# draft5_4lyr.net
KiCad netlist of a schematic drawn in EAGLE
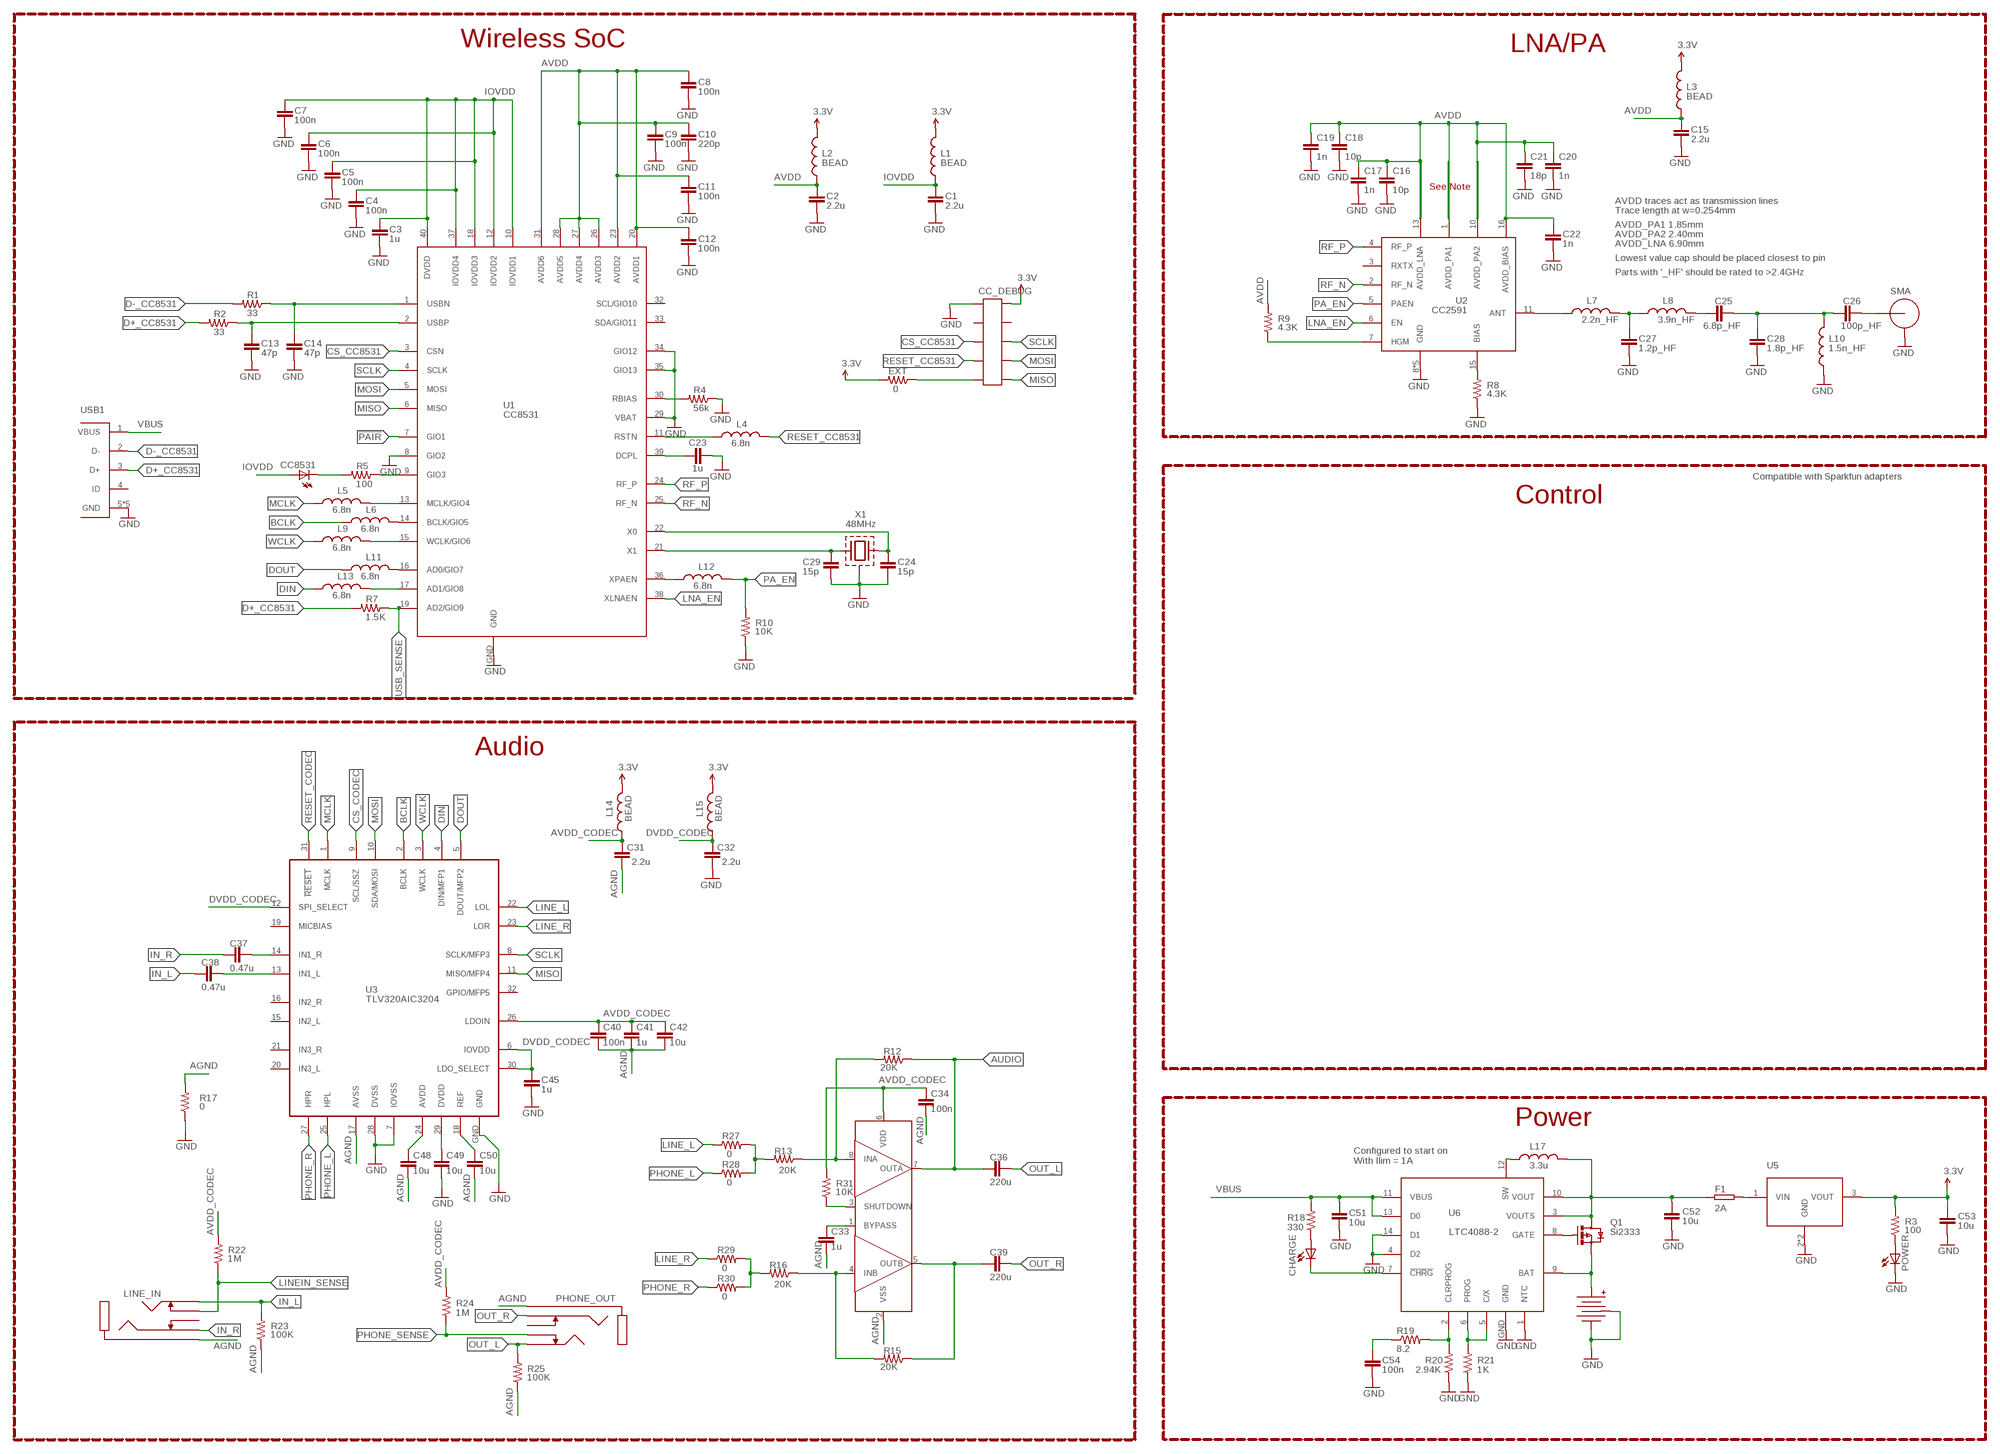
[diagram p0: schematic, sheet 1, part 1 of 2]
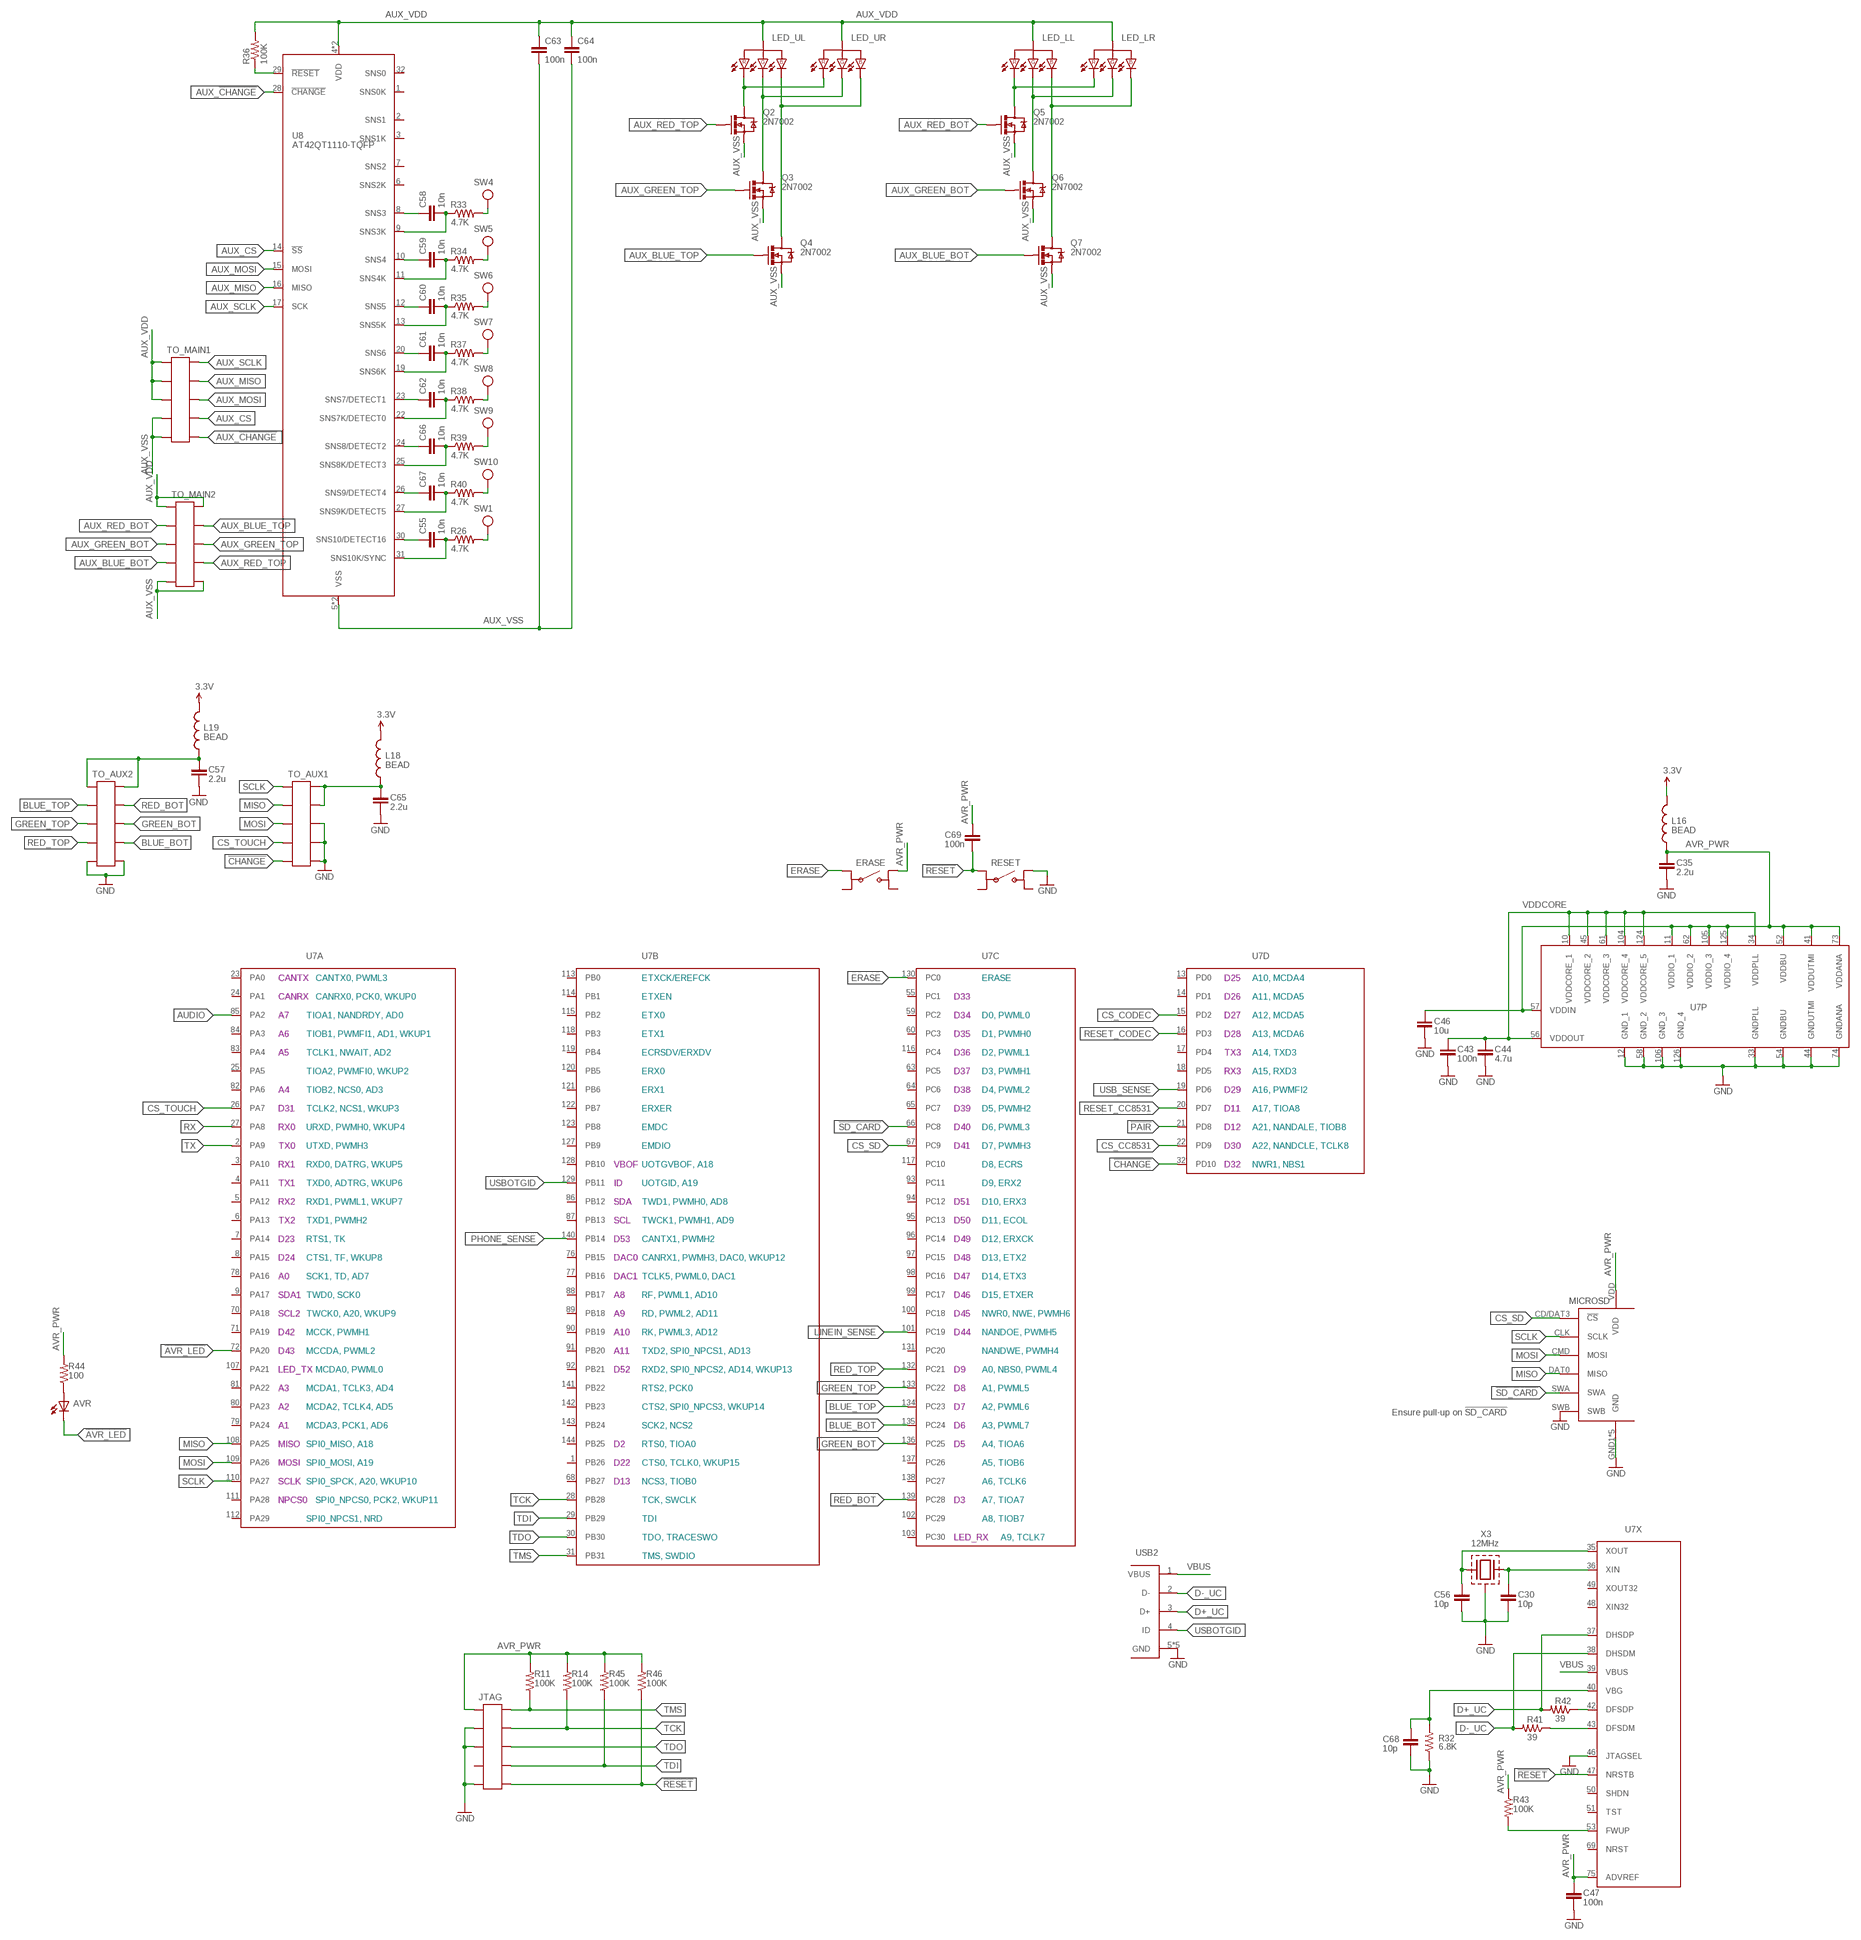
[diagram p1: schematic, sheet 1, part 2 of 2]

(export (version "E")
  (design (tool "Eeschema 10.0.6"))
  (components
    (comp (ref "AVR")
      (value "LED1206")
      (footprint "eagle-import:LED-1206")
      (libsource (lib "eagle-import") (part "LED1206"))
    )
    (comp (ref "BATTERY")
      (value "BATTERY-LIPO-JST")
      (footprint "eagle-import:1775469-2")
      (libsource (lib "eagle-import") (part "BATTERY-LIPO-JST"))
    )
    (comp (ref "C1")
      (value "2.2u")
      (footprint "eagle-import:C0603")
      (libsource (lib "eagle-import") (part "rcl_C-EUC0603"))
    )
    (comp (ref "C2")
      (value "2.2u")
      (footprint "eagle-import:C0603")
      (libsource (lib "eagle-import") (part "rcl_C-EUC0603"))
    )
    (comp (ref "C3")
      (value "1u")
      (footprint "eagle-import:C0603")
      (libsource (lib "eagle-import") (part "rcl_C-EUC0603"))
    )
    (comp (ref "C4")
      (value "100n")
      (footprint "eagle-import:C0603")
      (libsource (lib "eagle-import") (part "rcl_C-EUC0603"))
    )
    (comp (ref "C5")
      (value "100n")
      (footprint "eagle-import:C0603")
      (libsource (lib "eagle-import") (part "rcl_C-EUC0603"))
    )
    (comp (ref "C6")
      (value "100n")
      (footprint "eagle-import:C0603")
      (libsource (lib "eagle-import") (part "rcl_C-EUC0603"))
    )
    (comp (ref "C7")
      (value "100n")
      (footprint "eagle-import:C0603")
      (libsource (lib "eagle-import") (part "rcl_C-EUC0603"))
    )
    (comp (ref "C8")
      (value "100n")
      (footprint "eagle-import:C0603")
      (libsource (lib "eagle-import") (part "rcl_C-EUC0603"))
    )
    (comp (ref "C9")
      (value "100n")
      (footprint "eagle-import:C0603")
      (libsource (lib "eagle-import") (part "rcl_C-EUC0603"))
    )
    (comp (ref "C10")
      (value "220p")
      (footprint "eagle-import:C0603")
      (libsource (lib "eagle-import") (part "rcl_C-EUC0603"))
    )
    (comp (ref "C11")
      (value "100n")
      (footprint "eagle-import:C0603")
      (libsource (lib "eagle-import") (part "rcl_C-EUC0603"))
    )
    (comp (ref "C12")
      (value "100n")
      (footprint "eagle-import:C0603")
      (libsource (lib "eagle-import") (part "rcl_C-EUC0603"))
    )
    (comp (ref "C13")
      (value "47p")
      (footprint "eagle-import:C0603")
      (libsource (lib "eagle-import") (part "rcl_C-EUC0603"))
    )
    (comp (ref "C14")
      (value "47p")
      (footprint "eagle-import:C0603")
      (libsource (lib "eagle-import") (part "rcl_C-EUC0603"))
    )
    (comp (ref "C15")
      (value "2.2u")
      (footprint "eagle-import:C0603")
      (libsource (lib "eagle-import") (part "rcl_C-EUC0603"))
    )
    (comp (ref "C16")
      (value "10p")
      (footprint "eagle-import:C0603")
      (libsource (lib "eagle-import") (part "rcl_C-EUC0603"))
    )
    (comp (ref "C17")
      (value "1n")
      (footprint "eagle-import:C0603")
      (libsource (lib "eagle-import") (part "rcl_C-EUC0603"))
    )
    (comp (ref "C18")
      (value "10p")
      (footprint "eagle-import:C0603")
      (libsource (lib "eagle-import") (part "rcl_C-EUC0603"))
    )
    (comp (ref "C19")
      (value "1n")
      (footprint "eagle-import:C0603")
      (libsource (lib "eagle-import") (part "rcl_C-EUC0603"))
    )
    (comp (ref "C20")
      (value "1n")
      (footprint "eagle-import:C0603")
      (libsource (lib "eagle-import") (part "rcl_C-EUC0603"))
    )
    (comp (ref "C21")
      (value "18p")
      (footprint "eagle-import:C0603")
      (libsource (lib "eagle-import") (part "rcl_C-EUC0603"))
    )
    (comp (ref "C22")
      (value "1n")
      (footprint "eagle-import:C0603")
      (libsource (lib "eagle-import") (part "rcl_C-EUC0603"))
    )
    (comp (ref "C23")
      (value "1u")
      (footprint "eagle-import:C0603")
      (libsource (lib "eagle-import") (part "rcl_C-EUC0603"))
    )
    (comp (ref "C24")
      (value "15p")
      (footprint "eagle-import:C0603")
      (libsource (lib "eagle-import") (part "rcl_C-EUC0603"))
    )
    (comp (ref "C25")
      (value "6.8p_HF")
      (footprint "eagle-import:C0603")
      (libsource (lib "eagle-import") (part "rcl_C-EUC0603"))
    )
    (comp (ref "C26")
      (value "100p_HF")
      (footprint "eagle-import:C0603")
      (libsource (lib "eagle-import") (part "rcl_C-EUC0603"))
    )
    (comp (ref "C27")
      (value "1.2p_HF")
      (footprint "eagle-import:C0603")
      (libsource (lib "eagle-import") (part "rcl_C-EUC0603"))
    )
    (comp (ref "C28")
      (value "1.8p_HF")
      (footprint "eagle-import:C0603")
      (libsource (lib "eagle-import") (part "rcl_C-EUC0603"))
    )
    (comp (ref "C29")
      (value "15p")
      (footprint "eagle-import:C0603")
      (libsource (lib "eagle-import") (part "rcl_C-EUC0603"))
    )
    (comp (ref "C30")
      (value "10p")
      (footprint "eagle-import:C0603")
      (libsource (lib "eagle-import") (part "C-EUC0603"))
    )
    (comp (ref "C31")
      (value "2.2u")
      (footprint "eagle-import:C0603")
      (libsource (lib "eagle-import") (part "rcl_C-EUC0603"))
    )
    (comp (ref "C32")
      (value "2.2u")
      (footprint "eagle-import:C0603")
      (libsource (lib "eagle-import") (part "rcl_C-EUC0603"))
    )
    (comp (ref "C33")
      (value "1u")
      (footprint "eagle-import:C0603")
      (libsource (lib "eagle-import") (part "rcl_C-EUC0603"))
    )
    (comp (ref "C34")
      (value "100n")
      (footprint "eagle-import:C0603")
      (libsource (lib "eagle-import") (part "rcl_C-EUC0603"))
    )
    (comp (ref "C35")
      (value "2.2u")
      (footprint "eagle-import:C0603")
      (libsource (lib "eagle-import") (part "rcl_C-EUC0603"))
    )
    (comp (ref "C36")
      (value "220u")
      (footprint "eagle-import:C1210")
      (libsource (lib "eagle-import") (part "C-EUC1210"))
    )
    (comp (ref "C37")
      (value "0.47u")
      (footprint "eagle-import:C0603")
      (libsource (lib "eagle-import") (part "rcl_C-EUC0603"))
    )
    (comp (ref "C38")
      (value "0.47u")
      (footprint "eagle-import:C0603")
      (libsource (lib "eagle-import") (part "rcl_C-EUC0603"))
    )
    (comp (ref "C39")
      (value "220u")
      (footprint "eagle-import:C1210")
      (libsource (lib "eagle-import") (part "C-EUC1210"))
    )
    (comp (ref "C40")
      (value "100n")
      (footprint "eagle-import:C0603")
      (libsource (lib "eagle-import") (part "rcl_C-EUC0603"))
    )
    (comp (ref "C41")
      (value "1u")
      (footprint "eagle-import:C0603")
      (libsource (lib "eagle-import") (part "rcl_C-EUC0603"))
    )
    (comp (ref "C42")
      (value "10u")
      (footprint "eagle-import:C0603")
      (libsource (lib "eagle-import") (part "rcl_C-EUC0603"))
    )
    (comp (ref "C43")
      (value "100n")
      (footprint "eagle-import:C0603")
      (libsource (lib "eagle-import") (part "rcl_C-EUC0603"))
    )
    (comp (ref "C44")
      (value "4.7u")
      (footprint "eagle-import:C0603")
      (libsource (lib "eagle-import") (part "rcl_C-EUC0603"))
    )
    (comp (ref "C45")
      (value "1u")
      (footprint "eagle-import:C0603")
      (libsource (lib "eagle-import") (part "rcl_C-EUC0603"))
    )
    (comp (ref "C46")
      (value "10u")
      (footprint "eagle-import:C0603")
      (libsource (lib "eagle-import") (part "rcl_C-EUC0603"))
    )
    (comp (ref "C47")
      (value "100n")
      (footprint "eagle-import:C0603")
      (libsource (lib "eagle-import") (part "rcl_C-EUC0603"))
    )
    (comp (ref "C48")
      (value "10u")
      (footprint "eagle-import:C0603")
      (libsource (lib "eagle-import") (part "rcl_C-EUC0603"))
    )
    (comp (ref "C49")
      (value "10u")
      (footprint "eagle-import:C0603")
      (libsource (lib "eagle-import") (part "rcl_C-EUC0603"))
    )
    (comp (ref "C50")
      (value "10u")
      (footprint "eagle-import:C0603")
      (libsource (lib "eagle-import") (part "rcl_C-EUC0603"))
    )
    (comp (ref "C51")
      (value "10u")
      (footprint "eagle-import:C0603")
      (libsource (lib "eagle-import") (part "C-EUC0603"))
    )
    (comp (ref "C52")
      (value "10u")
      (footprint "eagle-import:C0603")
      (libsource (lib "eagle-import") (part "rcl_C-EUC0603"))
    )
    (comp (ref "C53")
      (value "10u")
      (footprint "eagle-import:C0603")
      (libsource (lib "eagle-import") (part "rcl_C-EUC0603"))
    )
    (comp (ref "C54")
      (value "100n")
      (footprint "eagle-import:C0603")
      (libsource (lib "eagle-import") (part "C-EUC0603"))
    )
    (comp (ref "C55")
      (value "10n")
      (footprint "eagle-import:C0603")
      (libsource (lib "eagle-import") (part "rcl_C-EUC0603"))
    )
    (comp (ref "C56")
      (value "10p")
      (footprint "eagle-import:C0603")
      (libsource (lib "eagle-import") (part "C-EUC0603"))
    )
    (comp (ref "C57")
      (value "2.2u")
      (footprint "eagle-import:C0603")
      (libsource (lib "eagle-import") (part "rcl_C-EUC0603"))
    )
    (comp (ref "C58")
      (value "10n")
      (footprint "eagle-import:C0603")
      (libsource (lib "eagle-import") (part "rcl_C-EUC0603"))
    )
    (comp (ref "C59")
      (value "10n")
      (footprint "eagle-import:C0603")
      (libsource (lib "eagle-import") (part "rcl_C-EUC0603"))
    )
    (comp (ref "C60")
      (value "10n")
      (footprint "eagle-import:C0603")
      (libsource (lib "eagle-import") (part "rcl_C-EUC0603"))
    )
    (comp (ref "C61")
      (value "10n")
      (footprint "eagle-import:C0603")
      (libsource (lib "eagle-import") (part "rcl_C-EUC0603"))
    )
    (comp (ref "C62")
      (value "10n")
      (footprint "eagle-import:C0603")
      (libsource (lib "eagle-import") (part "rcl_C-EUC0603"))
    )
    (comp (ref "C63")
      (value "100n")
      (footprint "eagle-import:C0603")
      (libsource (lib "eagle-import") (part "rcl_C-EUC0603"))
    )
    (comp (ref "C64")
      (value "100n")
      (footprint "eagle-import:C0603")
      (libsource (lib "eagle-import") (part "rcl_C-EUC0603"))
    )
    (comp (ref "C65")
      (value "2.2u")
      (footprint "eagle-import:C0603")
      (libsource (lib "eagle-import") (part "rcl_C-EUC0603"))
    )
    (comp (ref "C66")
      (value "10n")
      (footprint "eagle-import:C0603")
      (libsource (lib "eagle-import") (part "rcl_C-EUC0603"))
    )
    (comp (ref "C67")
      (value "10n")
      (footprint "eagle-import:C0603")
      (libsource (lib "eagle-import") (part "rcl_C-EUC0603"))
    )
    (comp (ref "C68")
      (value "10p")
      (footprint "eagle-import:C0603")
      (libsource (lib "eagle-import") (part "C-EUC0603"))
    )
    (comp (ref "C69")
      (value "100n")
      (footprint "eagle-import:C0603")
      (libsource (lib "eagle-import") (part "C-EUC0603"))
    )
    (comp (ref "CC8531")
      (value "LED1206")
      (footprint "eagle-import:LED-1206")
      (libsource (lib "eagle-import") (part "LED1206"))
    )
    (comp (ref "CC_DEBUG")
      (value "HEADER-10P-SMD-MALE2")
      (footprint "eagle-import:HEADER-10P-1.27MM")
      (libsource (lib "eagle-import") (part "HEADER-10P-SMD-MALE2"))
    )
    (comp (ref "CHARGE")
      (value "LED1206")
      (footprint "eagle-import:LED-1206")
      (libsource (lib "eagle-import") (part "LED1206"))
    )
    (comp (ref "ERASE")
      (value "TACT_SWITCH-PTS-525")
      (footprint "eagle-import:PTS-525")
      (libsource (lib "eagle-import") (part "TACT_SWITCH-PTS-525"))
    )
    (comp (ref "EXT")
      (value "0")
      (footprint "eagle-import:R0603")
      (libsource (lib "eagle-import") (part "rcl_R-US_R0603"))
    )
    (comp (ref "F1")
      (value "2A")
      (footprint "eagle-import:1210")
      (libsource (lib "eagle-import") (part "PTC_FUSE"))
    )
    (comp (ref "JTAG")
      (value "HEADER-10P-SMD-MALE2")
      (footprint "eagle-import:HEADER-10P-1.27MM")
      (libsource (lib "eagle-import") (part "HEADER-10P-SMD-MALE2"))
    )
    (comp (ref "L1")
      (value "BEAD")
      (footprint "eagle-import:0603")
      (libsource (lib "eagle-import") (part "INDUCTOR0603"))
    )
    (comp (ref "L2")
      (value "BEAD")
      (footprint "eagle-import:0603")
      (libsource (lib "eagle-import") (part "INDUCTOR0603"))
    )
    (comp (ref "L3")
      (value "BEAD")
      (footprint "eagle-import:0603")
      (libsource (lib "eagle-import") (part "INDUCTOR0603"))
    )
    (comp (ref "L4")
      (value "6.8n")
      (footprint "eagle-import:0603")
      (libsource (lib "eagle-import") (part "INDUCTOR0603"))
    )
    (comp (ref "L5")
      (value "6.8n")
      (footprint "eagle-import:0603")
      (libsource (lib "eagle-import") (part "INDUCTOR0603"))
    )
    (comp (ref "L6")
      (value "6.8n")
      (footprint "eagle-import:0603")
      (libsource (lib "eagle-import") (part "INDUCTOR0603"))
    )
    (comp (ref "L7")
      (value "2.2n_HF")
      (footprint "eagle-import:0603")
      (libsource (lib "eagle-import") (part "INDUCTOR0603"))
    )
    (comp (ref "L8")
      (value "3.9n_HF")
      (footprint "eagle-import:0603")
      (libsource (lib "eagle-import") (part "INDUCTOR0603"))
    )
    (comp (ref "L9")
      (value "6.8n")
      (footprint "eagle-import:0603")
      (libsource (lib "eagle-import") (part "INDUCTOR0603"))
    )
    (comp (ref "L10")
      (value "1.5n_HF")
      (footprint "eagle-import:0603")
      (libsource (lib "eagle-import") (part "INDUCTOR0603"))
    )
    (comp (ref "L11")
      (value "6.8n")
      (footprint "eagle-import:0603")
      (libsource (lib "eagle-import") (part "INDUCTOR0603"))
    )
    (comp (ref "L12")
      (value "6.8n")
      (footprint "eagle-import:0603")
      (libsource (lib "eagle-import") (part "INDUCTOR0603"))
    )
    (comp (ref "L13")
      (value "6.8n")
      (footprint "eagle-import:0603")
      (libsource (lib "eagle-import") (part "INDUCTOR0603"))
    )
    (comp (ref "L14")
      (value "BEAD")
      (footprint "eagle-import:0603")
      (libsource (lib "eagle-import") (part "INDUCTOR0603"))
    )
    (comp (ref "L15")
      (value "BEAD")
      (footprint "eagle-import:0603")
      (libsource (lib "eagle-import") (part "INDUCTOR0603"))
    )
    (comp (ref "L16")
      (value "BEAD")
      (footprint "eagle-import:0603")
      (libsource (lib "eagle-import") (part "INDUCTOR0603"))
    )
    (comp (ref "L17")
      (value "3.3u")
      (footprint "eagle-import:IFSC-1111AB-01")
      (libsource (lib "eagle-import") (part "IFSC-1111AB-01"))
    )
    (comp (ref "L18")
      (value "BEAD")
      (footprint "eagle-import:0603")
      (libsource (lib "eagle-import") (part "INDUCTOR0603"))
    )
    (comp (ref "L19")
      (value "BEAD")
      (footprint "eagle-import:0603")
      (libsource (lib "eagle-import") (part "INDUCTOR0603"))
    )
    (comp (ref "LED_LL")
      (value "LED_RGB")
      (footprint "eagle-import:PLCC-4")
      (libsource (lib "eagle-import") (part "LED_RGB"))
    )
    (comp (ref "LED_LR")
      (value "LED_RGB")
      (footprint "eagle-import:PLCC-4")
      (libsource (lib "eagle-import") (part "LED_RGB"))
    )
    (comp (ref "LED_UL")
      (value "LED_RGB")
      (footprint "eagle-import:PLCC-4")
      (libsource (lib "eagle-import") (part "LED_RGB"))
    )
    (comp (ref "LED_UR")
      (value "LED_RGB")
      (footprint "eagle-import:PLCC-4")
      (libsource (lib "eagle-import") (part "LED_RGB"))
    )
    (comp (ref "LINE_IN")
      (value "PHONE_SW-STX-35332-5N")
      (footprint "eagle-import:STX-35332-5N")
      (libsource (lib "eagle-import") (part "PHONE_SW-STX-35332-5N"))
    )
    (comp (ref "MICROSD")
      (value "MICROSD104031-0811")
      (footprint "eagle-import:MOLEX_104031-0811")
      (libsource (lib "eagle-import") (part "MICROSD104031-0811"))
    )
    (comp (ref "PHONE_OUT")
      (value "PHONE_SW-STX-35332-5N")
      (footprint "eagle-import:STX-35332-5N")
      (libsource (lib "eagle-import") (part "PHONE_SW-STX-35332-5N"))
    )
    (comp (ref "POWER")
      (value "LED1206")
      (footprint "eagle-import:LED-1206")
      (libsource (lib "eagle-import") (part "LED1206"))
    )
    (comp (ref "Q1")
      (value "Si2333")
      (footprint "eagle-import:SOT23-3")
      (libsource (lib "eagle-import") (part "MOSFET-PCHANNELSMD"))
    )
    (comp (ref "Q2")
      (value "2N7002")
      (footprint "eagle-import:SOT23-3")
      (libsource (lib "eagle-import") (part "MOSFET-NCHANNELSMD"))
    )
    (comp (ref "Q3")
      (value "2N7002")
      (footprint "eagle-import:SOT23-3")
      (libsource (lib "eagle-import") (part "MOSFET-NCHANNELSMD"))
    )
    (comp (ref "Q4")
      (value "2N7002")
      (footprint "eagle-import:SOT23-3")
      (libsource (lib "eagle-import") (part "MOSFET-NCHANNELSMD"))
    )
    (comp (ref "Q5")
      (value "2N7002")
      (footprint "eagle-import:SOT23-3")
      (libsource (lib "eagle-import") (part "MOSFET-NCHANNELSMD"))
    )
    (comp (ref "Q6")
      (value "2N7002")
      (footprint "eagle-import:SOT23-3")
      (libsource (lib "eagle-import") (part "MOSFET-NCHANNELSMD"))
    )
    (comp (ref "Q7")
      (value "2N7002")
      (footprint "eagle-import:SOT23-3")
      (libsource (lib "eagle-import") (part "MOSFET-NCHANNELSMD"))
    )
    (comp (ref "R1")
      (value "33")
      (footprint "eagle-import:R0603")
      (libsource (lib "eagle-import") (part "rcl_R-US_R0603"))
    )
    (comp (ref "R2")
      (value "33")
      (footprint "eagle-import:R0603")
      (libsource (lib "eagle-import") (part "rcl_R-US_R0603"))
    )
    (comp (ref "R3")
      (value "100")
      (footprint "eagle-import:R0603")
      (libsource (lib "eagle-import") (part "rcl_R-US_R0603"))
    )
    (comp (ref "R4")
      (value "56k")
      (footprint "eagle-import:R0603")
      (libsource (lib "eagle-import") (part "rcl_R-US_R0603"))
    )
    (comp (ref "R5")
      (value "100")
      (footprint "eagle-import:R0603")
      (libsource (lib "eagle-import") (part "rcl_R-US_R0603"))
    )
    (comp (ref "R7")
      (value "1.5K")
      (footprint "eagle-import:R0603")
      (libsource (lib "eagle-import") (part "rcl_R-US_R0603"))
    )
    (comp (ref "R8")
      (value "4.3K")
      (footprint "eagle-import:R0603")
      (libsource (lib "eagle-import") (part "rcl_R-US_R0603"))
    )
    (comp (ref "R9")
      (value "4.3K")
      (footprint "eagle-import:R0603")
      (libsource (lib "eagle-import") (part "rcl_R-US_R0603"))
    )
    (comp (ref "R10")
      (value "10K")
      (footprint "eagle-import:R0603")
      (libsource (lib "eagle-import") (part "rcl_R-US_R0603"))
    )
    (comp (ref "R11")
      (value "100K")
      (footprint "eagle-import:R0603")
      (libsource (lib "eagle-import") (part "rcl_R-US_R0603"))
    )
    (comp (ref "R12")
      (value "20K")
      (footprint "eagle-import:R0603")
      (libsource (lib "eagle-import") (part "R-US_R0603"))
    )
    (comp (ref "R13")
      (value "20K")
      (footprint "eagle-import:R0603")
      (libsource (lib "eagle-import") (part "R-US_R0603"))
    )
    (comp (ref "R14")
      (value "100K")
      (footprint "eagle-import:R0603")
      (libsource (lib "eagle-import") (part "rcl_R-US_R0603"))
    )
    (comp (ref "R15")
      (value "20K")
      (footprint "eagle-import:R0603")
      (libsource (lib "eagle-import") (part "R-US_R0603"))
    )
    (comp (ref "R16")
      (value "20K")
      (footprint "eagle-import:R0603")
      (libsource (lib "eagle-import") (part "R-US_R0603"))
    )
    (comp (ref "R17")
      (value "0")
      (footprint "eagle-import:R0603")
      (libsource (lib "eagle-import") (part "rcl_R-US_R0603"))
    )
    (comp (ref "R18")
      (value "330")
      (footprint "eagle-import:R0603")
      (libsource (lib "eagle-import") (part "R-US_R0603"))
    )
    (comp (ref "R19")
      (value "8.2")
      (footprint "eagle-import:R0603")
      (libsource (lib "eagle-import") (part "R-US_R0603"))
    )
    (comp (ref "R20")
      (value "2.94K")
      (footprint "eagle-import:R0603")
      (libsource (lib "eagle-import") (part "R-US_R0603"))
    )
    (comp (ref "R21")
      (value "1K")
      (footprint "eagle-import:R0603")
      (libsource (lib "eagle-import") (part "R-US_R0603"))
    )
    (comp (ref "R22")
      (value "1M")
      (footprint "eagle-import:R0603")
      (libsource (lib "eagle-import") (part "rcl_R-US_R0603"))
    )
    (comp (ref "R23")
      (value "100K")
      (footprint "eagle-import:R0603")
      (libsource (lib "eagle-import") (part "rcl_R-US_R0603"))
    )
    (comp (ref "R24")
      (value "1M")
      (footprint "eagle-import:R0603")
      (libsource (lib "eagle-import") (part "rcl_R-US_R0603"))
    )
    (comp (ref "R25")
      (value "100K")
      (footprint "eagle-import:R0603")
      (libsource (lib "eagle-import") (part "rcl_R-US_R0603"))
    )
    (comp (ref "R26")
      (value "4.7K")
      (footprint "eagle-import:R0603")
      (libsource (lib "eagle-import") (part "rcl_R-US_R0603"))
    )
    (comp (ref "R27")
      (value "0")
      (footprint "eagle-import:R0603")
      (libsource (lib "eagle-import") (part "R-US_R0603"))
    )
    (comp (ref "R28")
      (value "0")
      (footprint "eagle-import:R0603")
      (libsource (lib "eagle-import") (part "R-US_R0603"))
    )
    (comp (ref "R29")
      (value "0")
      (footprint "eagle-import:R0603")
      (libsource (lib "eagle-import") (part "R-US_R0603"))
    )
    (comp (ref "R30")
      (value "0")
      (footprint "eagle-import:R0603")
      (libsource (lib "eagle-import") (part "R-US_R0603"))
    )
    (comp (ref "R31")
      (value "10K")
      (footprint "eagle-import:R0603")
      (libsource (lib "eagle-import") (part "rcl_R-US_R0603"))
    )
    (comp (ref "R32")
      (value "6.8K")
      (footprint "eagle-import:R0603")
      (libsource (lib "eagle-import") (part "rcl_R-US_R0603"))
    )
    (comp (ref "R33")
      (value "4.7K")
      (footprint "eagle-import:R0603")
      (libsource (lib "eagle-import") (part "rcl_R-US_R0603"))
    )
    (comp (ref "R34")
      (value "4.7K")
      (footprint "eagle-import:R0603")
      (libsource (lib "eagle-import") (part "rcl_R-US_R0603"))
    )
    (comp (ref "R35")
      (value "4.7K")
      (footprint "eagle-import:R0603")
      (libsource (lib "eagle-import") (part "rcl_R-US_R0603"))
    )
    (comp (ref "R36")
      (value "100K")
      (footprint "eagle-import:R0603")
      (libsource (lib "eagle-import") (part "rcl_R-US_R0603"))
    )
    (comp (ref "R37")
      (value "4.7K")
      (footprint "eagle-import:R0603")
      (libsource (lib "eagle-import") (part "rcl_R-US_R0603"))
    )
    (comp (ref "R38")
      (value "4.7K")
      (footprint "eagle-import:R0603")
      (libsource (lib "eagle-import") (part "rcl_R-US_R0603"))
    )
    (comp (ref "R39")
      (value "4.7K")
      (footprint "eagle-import:R0603")
      (libsource (lib "eagle-import") (part "rcl_R-US_R0603"))
    )
    (comp (ref "R40")
      (value "4.7K")
      (footprint "eagle-import:R0603")
      (libsource (lib "eagle-import") (part "rcl_R-US_R0603"))
    )
    (comp (ref "R41")
      (value "39")
      (footprint "eagle-import:R0603")
      (libsource (lib "eagle-import") (part "rcl_R-US_R0603"))
    )
    (comp (ref "R42")
      (value "39")
      (footprint "eagle-import:R0603")
      (libsource (lib "eagle-import") (part "rcl_R-US_R0603"))
    )
    (comp (ref "R43")
      (value "100K")
      (footprint "eagle-import:R0603")
      (libsource (lib "eagle-import") (part "rcl_R-US_R0603"))
    )
    (comp (ref "R44")
      (value "100")
      (footprint "eagle-import:R0603")
      (libsource (lib "eagle-import") (part "rcl_R-US_R0603"))
    )
    (comp (ref "R45")
      (value "100K")
      (footprint "eagle-import:R0603")
      (libsource (lib "eagle-import") (part "rcl_R-US_R0603"))
    )
    (comp (ref "R46")
      (value "100K")
      (footprint "eagle-import:R0603")
      (libsource (lib "eagle-import") (part "rcl_R-US_R0603"))
    )
    (comp (ref "RESET")
      (value "TACT_SWITCH-PTS-525")
      (footprint "eagle-import:PTS-525")
      (libsource (lib "eagle-import") (part "TACT_SWITCH-PTS-525"))
    )
    (comp (ref "SMA")
      (value "SMA-REVSMA-0.62")
      (footprint "eagle-import:CONREVSMA003.062")
      (libsource (lib "eagle-import") (part "SMA-REVSMA-0.62"))
    )
    (comp (ref "SW1")
      (value "TOUCH_PAD-CIRCLE-15MM")
      (footprint "eagle-import:TOUCH-CIRCLE-15MM")
      (libsource (lib "eagle-import") (part "TOUCH_PAD-CIRCLE-15MM"))
    )
    (comp (ref "SW4")
      (value "TOUCH_PAD-CIRCLE-15MM")
      (footprint "eagle-import:TOUCH-CIRCLE-15MM")
      (libsource (lib "eagle-import") (part "TOUCH_PAD-CIRCLE-15MM"))
    )
    (comp (ref "SW5")
      (value "TOUCH_PAD-CIRCLE-15MM")
      (footprint "eagle-import:TOUCH-CIRCLE-15MM")
      (libsource (lib "eagle-import") (part "TOUCH_PAD-CIRCLE-15MM"))
    )
    (comp (ref "SW6")
      (value "TOUCH_PAD-CIRCLE-15MM")
      (footprint "eagle-import:TOUCH-CIRCLE-15MM")
      (libsource (lib "eagle-import") (part "TOUCH_PAD-CIRCLE-15MM"))
    )
    (comp (ref "SW7")
      (value "TOUCH_PAD-CIRCLE-15MM")
      (footprint "eagle-import:TOUCH-CIRCLE-15MM")
      (libsource (lib "eagle-import") (part "TOUCH_PAD-CIRCLE-15MM"))
    )
    (comp (ref "SW8")
      (value "TOUCH_PAD-CIRCLE-15MM")
      (footprint "eagle-import:TOUCH-CIRCLE-15MM")
      (libsource (lib "eagle-import") (part "TOUCH_PAD-CIRCLE-15MM"))
    )
    (comp (ref "SW9")
      (value "TOUCH_PAD-CIRCLE-15MM")
      (footprint "eagle-import:TOUCH-CIRCLE-15MM")
      (libsource (lib "eagle-import") (part "TOUCH_PAD-CIRCLE-15MM"))
    )
    (comp (ref "SW10")
      (value "TOUCH_PAD-CIRCLE-15MM")
      (footprint "eagle-import:TOUCH-CIRCLE-15MM")
      (libsource (lib "eagle-import") (part "TOUCH_PAD-CIRCLE-15MM"))
    )
    (comp (ref "TO_AUX1")
      (value "HEADER-10P-SMD-2MM-FEMALE")
      (footprint "eagle-import:M22-63405")
      (libsource (lib "eagle-import") (part "HEADER-10P-SMD-2MM-FEMALE"))
    )
    (comp (ref "TO_AUX2")
      (value "HEADER-10P-SMD-2MM-FEMALE")
      (footprint "eagle-import:M22-63405")
      (libsource (lib "eagle-import") (part "HEADER-10P-SMD-2MM-FEMALE"))
    )
    (comp (ref "TO_MAIN1")
      (value "HEADER-10P-SMD-2MM-MALE")
      (footprint "eagle-import:M22-53205")
      (libsource (lib "eagle-import") (part "HEADER-10P-SMD-2MM-MALE"))
    )
    (comp (ref "TO_MAIN2")
      (value "HEADER-10P-SMD-2MM-MALE")
      (footprint "eagle-import:M22-53205")
      (libsource (lib "eagle-import") (part "HEADER-10P-SMD-2MM-MALE"))
    )
    (comp (ref "U1")
      (value "CC8531")
      (footprint "eagle-import:S-PVQFN-N40")
      (libsource (lib "eagle-import") (part "CC8531"))
    )
    (comp (ref "U2")
      (value "CC2591")
      (footprint "eagle-import:S-PVQFN-N16")
      (libsource (lib "eagle-import") (part "CC2591"))
    )
    (comp (ref "U3")
      (value "TLV320AIC3204")
      (footprint "eagle-import:S-PVQFN-N32")
      (libsource (lib "eagle-import") (part "TLV320AIC3204"))
    )
    (comp (ref "U5")
      (value "MCP1826-SOT223")
      (footprint "eagle-import:SOT-223")
      (libsource (lib "eagle-import") (part "MCP1826-SOT223"))
    )
    (comp (ref "U6")
      (value "LTC4088-2")
      (footprint "eagle-import:DFN-14")
      (libsource (lib "eagle-import") (part "LTC4088-1/2"))
    )
    (comp (ref "U7")
      (value "ATSAM3X8E_ALT-LQFP-144")
      (footprint "eagle-import:LQFP-144")
      (libsource (lib "eagle-import") (part "ATSAM3X8E_ALT-LQFP-144"))
    )
    (comp (ref "U8")
      (value "AT42QT1110-TQFP")
      (footprint "eagle-import:S-PQFP-N32")
      (libsource (lib "eagle-import") (part "AT42QT1110-TQFP"))
    )
    (comp (ref "U9")
      (value "LM4881")
      (footprint "eagle-import:SO08")
      (libsource (lib "eagle-import") (part "LM4881"))
    )
    (comp (ref "USB1")
      (value "USB_MICRO_AB")
      (footprint "eagle-import:USB_MICRO_AB")
      (libsource (lib "eagle-import") (part "USB_MICRO_AB"))
    )
    (comp (ref "USB2")
      (value "USB_MICRO_AB")
      (footprint "eagle-import:USB_MICRO_AB")
      (libsource (lib "eagle-import") (part "USB_MICRO_AB"))
    )
    (comp (ref "X1")
      (value "48MHz")
      (footprint "eagle-import:ABM3C")
      (libsource (lib "eagle-import") (part "XTAL-ABRACONABM3C"))
    )
    (comp (ref "X3")
      (value "12MHz")
      (footprint "eagle-import:ABM8G")
      (libsource (lib "eagle-import") (part "XTAL-ABRACONABM8G"))
    )
  )
  (nets
    (net (code "1") (name "/AGND") (class "Default")
      (node (ref "C31") (pin "2") (pinfunction "2_2") (pintype "passive"))
      (node (ref "C33") (pin "2") (pinfunction "2_2") (pintype "passive"))
      (node (ref "C34") (pin "2") (pinfunction "2_2") (pintype "passive"))
      (node (ref "C40") (pin "2") (pinfunction "2_2") (pintype "passive"))
      (node (ref "C41") (pin "2") (pinfunction "2_2") (pintype "passive"))
      (node (ref "C42") (pin "2") (pinfunction "2_2") (pintype "passive"))
      (node (ref "C48") (pin "2") (pinfunction "2_2") (pintype "passive"))
      (node (ref "C50") (pin "2") (pinfunction "2_2") (pintype "passive"))
      (node (ref "LINE_IN") (pin "5") (pinfunction "GND_5") (pintype "bidirectional"))
      (node (ref "PHONE_OUT") (pin "5") (pinfunction "GND_5") (pintype "bidirectional"))
      (node (ref "R17") (pin "2") (pinfunction "2_2") (pintype "passive"))
      (node (ref "R23") (pin "1") (pinfunction "1_1") (pintype "passive"))
      (node (ref "R25") (pin "1") (pinfunction "1_1") (pintype "passive"))
      (node (ref "U3") (pin "17") (pinfunction "AVSS_17") (pintype "bidirectional"))
      (node (ref "U9") (pin "2") (pinfunction "VSS_2") (pintype "bidirectional"))
    )
    (net (code "2") (name "/AUX_VDD") (class "Default")
      (node (ref "C63") (pin "1") (pinfunction "1_1") (pintype "passive"))
      (node (ref "C64") (pin "1") (pinfunction "1_1") (pintype "passive"))
      (node (ref "LED_LL") (pin "2") (pinfunction "A_2") (pintype "passive"))
      (node (ref "LED_LL") (pin "2-2") (pinfunction "A_2-2") (pintype "passive"))
      (node (ref "LED_LR") (pin "2") (pinfunction "A_2") (pintype "passive"))
      (node (ref "LED_LR") (pin "2-2") (pinfunction "A_2-2") (pintype "passive"))
      (node (ref "LED_UL") (pin "2") (pinfunction "A_2") (pintype "passive"))
      (node (ref "LED_UL") (pin "2-2") (pinfunction "A_2-2") (pintype "passive"))
      (node (ref "LED_UR") (pin "2") (pinfunction "A_2") (pintype "passive"))
      (node (ref "LED_UR") (pin "2-2") (pinfunction "A_2-2") (pintype "passive"))
      (node (ref "R36") (pin "2") (pinfunction "2_2") (pintype "passive"))
      (node (ref "TO_MAIN1") (pin "1") (pinfunction "1_1") (pintype "bidirectional"))
      (node (ref "TO_MAIN1") (pin "3") (pinfunction "3_3") (pintype "bidirectional"))
      (node (ref "TO_MAIN1") (pin "5") (pinfunction "5_5") (pintype "bidirectional"))
      (node (ref "TO_MAIN2") (pin "1") (pinfunction "1_1") (pintype "bidirectional"))
      (node (ref "TO_MAIN2") (pin "2") (pinfunction "2_2") (pintype "bidirectional"))
      (node (ref "U8") (pin "18") (pinfunction "VDD_18") (pintype "bidirectional"))
      (node (ref "U8") (pin "4") (pinfunction "VDD_4") (pintype "bidirectional"))
    )
    (net (code "3") (name "/AUX_VSS") (class "Default")
      (node (ref "C63") (pin "2") (pinfunction "2_2") (pintype "passive"))
      (node (ref "C64") (pin "2") (pinfunction "2_2") (pintype "passive"))
      (node (ref "Q2") (pin "2") (pinfunction "S_2") (pintype "passive"))
      (node (ref "Q3") (pin "2") (pinfunction "S_2") (pintype "passive"))
      (node (ref "Q4") (pin "2") (pinfunction "S_2") (pintype "passive"))
      (node (ref "Q5") (pin "2") (pinfunction "S_2") (pintype "passive"))
      (node (ref "Q6") (pin "2") (pinfunction "S_2") (pintype "passive"))
      (node (ref "Q7") (pin "2") (pinfunction "S_2") (pintype "passive"))
      (node (ref "TO_MAIN1") (pin "7") (pinfunction "7_7") (pintype "bidirectional"))
      (node (ref "TO_MAIN1") (pin "9") (pinfunction "9_9") (pintype "bidirectional"))
      (node (ref "TO_MAIN2") (pin "10") (pinfunction "10_10") (pintype "bidirectional"))
      (node (ref "TO_MAIN2") (pin "9") (pinfunction "9_9") (pintype "bidirectional"))
      (node (ref "U8") (pin "21") (pinfunction "VSS_21") (pintype "bidirectional"))
      (node (ref "U8") (pin "5") (pinfunction "VSS_5") (pintype "bidirectional"))
    )
    (net (code "4") (name "/AUX_~{CHANGE}") (class "Default")
      (node (ref "TO_MAIN1") (pin "10") (pinfunction "10_10") (pintype "bidirectional"))
      (node (ref "U8") (pin "28") (pinfunction "~{CHANGE}_28") (pintype "bidirectional"))
    )
    (net (code "5") (name "/AVDD") (class "Default")
      (node (ref "C10") (pin "1") (pinfunction "1_1") (pintype "passive"))
      (node (ref "C11") (pin "1") (pinfunction "1_1") (pintype "passive"))
      (node (ref "C12") (pin "1") (pinfunction "1_1") (pintype "passive"))
      (node (ref "C15") (pin "1") (pinfunction "1_1") (pintype "passive"))
      (node (ref "C16") (pin "1") (pinfunction "1_1") (pintype "passive"))
      (node (ref "C17") (pin "1") (pinfunction "1_1") (pintype "passive"))
      (node (ref "C18") (pin "1") (pinfunction "1_1") (pintype "passive"))
      (node (ref "C19") (pin "1") (pinfunction "1_1") (pintype "passive"))
      (node (ref "C2") (pin "1") (pinfunction "1_1") (pintype "passive"))
      (node (ref "C20") (pin "1") (pinfunction "1_1") (pintype "passive"))
      (node (ref "C21") (pin "1") (pinfunction "1_1") (pintype "passive"))
      (node (ref "C22") (pin "1") (pinfunction "1_1") (pintype "passive"))
      (node (ref "C8") (pin "1") (pinfunction "1_1") (pintype "passive"))
      (node (ref "C9") (pin "1") (pinfunction "1_1") (pintype "passive"))
      (node (ref "L2") (pin "1") (pinfunction "1_1") (pintype "passive"))
      (node (ref "L3") (pin "1") (pinfunction "1_1") (pintype "passive"))
      (node (ref "R9") (pin "2") (pinfunction "2_2") (pintype "passive"))
      (node (ref "U1") (pin "20") (pinfunction "AVDD1_20") (pintype "bidirectional"))
      (node (ref "U1") (pin "23") (pinfunction "AVDD2_23") (pintype "bidirectional"))
      (node (ref "U1") (pin "26") (pinfunction "AVDD3_26") (pintype "bidirectional"))
      (node (ref "U1") (pin "27") (pinfunction "AVDD4_27") (pintype "bidirectional"))
      (node (ref "U1") (pin "28") (pinfunction "AVDD5_28") (pintype "bidirectional"))
      (node (ref "U1") (pin "31") (pinfunction "AVDD6_31") (pintype "bidirectional"))
      (node (ref "U2") (pin "1") (pinfunction "AVDD_PA1_1") (pintype "bidirectional"))
      (node (ref "U2") (pin "10") (pinfunction "AVDD_PA2_10") (pintype "bidirectional"))
      (node (ref "U2") (pin "13") (pinfunction "AVDD_LNA_13") (pintype "bidirectional"))
      (node (ref "U2") (pin "16") (pinfunction "AVDD_BIAS_16") (pintype "bidirectional"))
    )
    (net (code "6") (name "/AVDD_CODEC") (class "Default")
      (node (ref "C31") (pin "1") (pinfunction "1_1") (pintype "passive"))
      (node (ref "C34") (pin "1") (pinfunction "1_1") (pintype "passive"))
      (node (ref "C40") (pin "1") (pinfunction "1_1") (pintype "passive"))
      (node (ref "C41") (pin "1") (pinfunction "1_1") (pintype "passive"))
      (node (ref "C42") (pin "1") (pinfunction "1_1") (pintype "passive"))
      (node (ref "L14") (pin "1") (pinfunction "1_1") (pintype "passive"))
      (node (ref "R22") (pin "2") (pinfunction "2_2") (pintype "passive"))
      (node (ref "R24") (pin "2") (pinfunction "2_2") (pintype "passive"))
      (node (ref "R31") (pin "2") (pinfunction "2_2") (pintype "passive"))
      (node (ref "U3") (pin "26") (pinfunction "LDOIN_26") (pintype "bidirectional"))
      (node (ref "U9") (pin "6") (pinfunction "VDD_6") (pintype "bidirectional"))
    )
    (net (code "7") (name "/AVR_PWR") (class "Default")
      (node (ref "C35") (pin "1") (pinfunction "1_1") (pintype "passive"))
      (node (ref "C46") (pin "1") (pinfunction "1_1") (pintype "passive"))
      (node (ref "C47") (pin "1") (pinfunction "1_1") (pintype "passive"))
      (node (ref "C69") (pin "1") (pinfunction "1_1") (pintype "passive"))
      (node (ref "ERASE") (pin "3") (pinfunction "3_3") (pintype "bidirectional"))
      (node (ref "JTAG") (pin "1") (pinfunction "1_1") (pintype "bidirectional"))
      (node (ref "L16") (pin "1") (pinfunction "1_1") (pintype "passive"))
      (node (ref "MICROSD") (pin "VDD") (pinfunction "VDD_VDD") (pintype "bidirectional"))
      (node (ref "R11") (pin "2") (pinfunction "2_2") (pintype "passive"))
      (node (ref "R14") (pin "2") (pinfunction "2_2") (pintype "passive"))
      (node (ref "R43") (pin "1") (pinfunction "1_1") (pintype "passive"))
      (node (ref "R44") (pin "2") (pinfunction "2_2") (pintype "passive"))
      (node (ref "R45") (pin "2") (pinfunction "2_2") (pintype "passive"))
      (node (ref "R46") (pin "2") (pinfunction "2_2") (pintype "passive"))
      (node (ref "U7") (pin "105") (pinfunction "VDDIO_3_105") (pintype "bidirectional"))
      (node (ref "U7") (pin "11") (pinfunction "VDDIO_1_11") (pintype "bidirectional"))
      (node (ref "U7") (pin "125") (pinfunction "VDDIO_4_125") (pintype "bidirectional"))
      (node (ref "U7") (pin "41") (pinfunction "VDDUTMI_41") (pintype "bidirectional"))
      (node (ref "U7") (pin "52") (pinfunction "VDDBU_52") (pintype "bidirectional"))
      (node (ref "U7") (pin "57") (pinfunction "VDDIN_57") (pintype "bidirectional"))
      (node (ref "U7") (pin "62") (pinfunction "VDDIO_2_62") (pintype "bidirectional"))
      (node (ref "U7") (pin "73") (pinfunction "VDDANA_73") (pintype "bidirectional"))
      (node (ref "U7") (pin "75") (pinfunction "ADVREF_75") (pintype "bidirectional"))
    )
    (net (code "8") (name "/DVDD_CODEC") (class "Default")
      (node (ref "C32") (pin "1") (pinfunction "1_1") (pintype "passive"))
      (node (ref "C45") (pin "1") (pinfunction "1_1") (pintype "passive"))
      (node (ref "L15") (pin "1") (pinfunction "1_1") (pintype "passive"))
      (node (ref "U3") (pin "12") (pinfunction "SPI_SELECT_12") (pintype "bidirectional"))
      (node (ref "U3") (pin "30") (pinfunction "LDO_SELECT_30") (pintype "bidirectional"))
      (node (ref "U3") (pin "6") (pinfunction "IOVDD_6") (pintype "bidirectional"))
    )
    (net (code "9") (name "/IOVDD") (class "Default")
      (node (ref "C1") (pin "1") (pinfunction "1_1") (pintype "passive"))
      (node (ref "C3") (pin "1") (pinfunction "1_1") (pintype "passive"))
      (node (ref "C4") (pin "1") (pinfunction "1_1") (pintype "passive"))
      (node (ref "C5") (pin "1") (pinfunction "1_1") (pintype "passive"))
      (node (ref "C6") (pin "1") (pinfunction "1_1") (pintype "passive"))
      (node (ref "C7") (pin "1") (pinfunction "1_1") (pintype "passive"))
      (node (ref "CC8531") (pin "A") (pinfunction "A_A") (pintype "passive"))
      (node (ref "L1") (pin "1") (pinfunction "1_1") (pintype "passive"))
      (node (ref "U1") (pin "10") (pinfunction "IOVDD1_10") (pintype "bidirectional"))
      (node (ref "U1") (pin "12") (pinfunction "IOVDD2_12") (pintype "bidirectional"))
      (node (ref "U1") (pin "18") (pinfunction "IOVDD3_18") (pintype "bidirectional"))
      (node (ref "U1") (pin "37") (pinfunction "IOVDD4_37") (pintype "bidirectional"))
      (node (ref "U1") (pin "40") (pinfunction "DVDD_40") (pintype "bidirectional"))
    )
    (net (code "10") (name "/VBUS") (class "Default")
      (node (ref "C51") (pin "1") (pinfunction "1_1") (pintype "passive"))
      (node (ref "R18") (pin "2") (pinfunction "2_2") (pintype "passive"))
      (node (ref "U6") (pin "11") (pinfunction "VBUS_11") (pintype "bidirectional"))
      (node (ref "U6") (pin "13") (pinfunction "D0_13") (pintype "bidirectional"))
      (node (ref "U7") (pin "39") (pinfunction "VBUS_39") (pintype "bidirectional"))
      (node (ref "USB1") (pin "1") (pinfunction "VBUS_1") (pintype "bidirectional"))
      (node (ref "USB2") (pin "1") (pinfunction "VBUS_1") (pintype "bidirectional"))
    )
    (net (code "11") (name "/VDDCORE") (class "Default")
      (node (ref "C43") (pin "1") (pinfunction "1_1") (pintype "passive"))
      (node (ref "C44") (pin "1") (pinfunction "1_1") (pintype "passive"))
      (node (ref "U7") (pin "10") (pinfunction "VDDCORE_1_10") (pintype "bidirectional"))
      (node (ref "U7") (pin "104") (pinfunction "VDDCORE_4_104") (pintype "bidirectional"))
      (node (ref "U7") (pin "124") (pinfunction "VDDCORE_5_124") (pintype "bidirectional"))
      (node (ref "U7") (pin "34") (pinfunction "VDDPLL_34") (pintype "bidirectional"))
      (node (ref "U7") (pin "45") (pinfunction "VDDCORE_2_45") (pintype "bidirectional"))
      (node (ref "U7") (pin "56") (pinfunction "VDDOUT_56") (pintype "bidirectional"))
      (node (ref "U7") (pin "61") (pinfunction "VDDCORE_3_61") (pintype "bidirectional"))
    )
    (net (code "12") (name "/~{AVR_LED}") (class "Default")
      (node (ref "AVR") (pin "C") (pinfunction "C_C") (pintype "passive"))
      (node (ref "U7") (pin "72") (pinfunction "PA20_72") (pintype "bidirectional"))
    )
    (net (code "13") (name "/~{CHANGE}") (class "Default")
      (node (ref "TO_AUX1") (pin "9") (pinfunction "9_9") (pintype "bidirectional"))
      (node (ref "U7") (pin "32") (pinfunction "PD10_32") (pintype "bidirectional"))
    )
    (net (code "14") (name "/~{PAIR}") (class "Default")
      (node (ref "U1") (pin "7") (pinfunction "GIO1_7") (pintype "bidirectional"))
      (node (ref "U7") (pin "21") (pinfunction "PD8_21") (pintype "bidirectional"))
    )
    (net (code "15") (name "/~{RESET}") (class "Default")
      (node (ref "C69") (pin "2") (pinfunction "2_2") (pintype "passive"))
      (node (ref "JTAG") (pin "10") (pinfunction "10_10") (pintype "bidirectional"))
      (node (ref "R46") (pin "1") (pinfunction "1_1") (pintype "passive"))
      (node (ref "RESET") (pin "1") (pinfunction "1_1") (pintype "bidirectional"))
      (node (ref "U7") (pin "47") (pinfunction "NRSTB_47") (pintype "bidirectional"))
    )
    (net (code "16") (name "/~{SD_CARD}") (class "Default")
      (node (ref "MICROSD") (pin "SWA") (pinfunction "SWA_SWA") (pintype "bidirectional"))
      (node (ref "U7") (pin "66") (pinfunction "PC8_66") (pintype "bidirectional"))
    )
    (net (code "17") (name "3.3V") (class "Default")
      (node (ref "C53") (pin "1") (pinfunction "1_1") (pintype "passive"))
      (node (ref "CC_DEBUG") (pin "2") (pinfunction "2_2") (pintype "bidirectional"))
      (node (ref "EXT") (pin "2") (pinfunction "2_2") (pintype "passive"))
      (node (ref "L1") (pin "2") (pinfunction "2_2") (pintype "passive"))
      (node (ref "L14") (pin "2") (pinfunction "2_2") (pintype "passive"))
      (node (ref "L15") (pin "2") (pinfunction "2_2") (pintype "passive"))
      (node (ref "L16") (pin "2") (pinfunction "2_2") (pintype "passive"))
      (node (ref "L18") (pin "2") (pinfunction "2_2") (pintype "passive"))
      (node (ref "L19") (pin "2") (pinfunction "2_2") (pintype "passive"))
      (node (ref "L2") (pin "2") (pinfunction "2_2") (pintype "passive"))
      (node (ref "L3") (pin "2") (pinfunction "2_2") (pintype "passive"))
      (node (ref "R3") (pin "2") (pinfunction "2_2") (pintype "passive"))
      (node (ref "U5") (pin "3") (pinfunction "VOUT_3") (pintype "bidirectional"))
    )
    (net (code "18") (name "AUDIO") (class "Default")
      (node (ref "C36") (pin "1") (pinfunction "1_1") (pintype "passive"))
      (node (ref "R12") (pin "1") (pinfunction "1_1") (pintype "passive"))
      (node (ref "U7") (pin "85") (pinfunction "PA2_85") (pintype "bidirectional"))
      (node (ref "U9") (pin "7") (pinfunction "OUTA_7") (pintype "bidirectional"))
    )
    (net (code "19") (name "AUX_BLUE_BOT") (class "Default")
      (node (ref "Q7") (pin "1") (pinfunction "G_1") (pintype "passive"))
      (node (ref "TO_MAIN2") (pin "7") (pinfunction "7_7") (pintype "bidirectional"))
    )
    (net (code "20") (name "AUX_BLUE_TOP") (class "Default")
      (node (ref "Q4") (pin "1") (pinfunction "G_1") (pintype "passive"))
      (node (ref "TO_MAIN2") (pin "4") (pinfunction "4_4") (pintype "bidirectional"))
    )
    (net (code "21") (name "AUX_CS") (class "Default")
      (node (ref "TO_MAIN1") (pin "8") (pinfunction "8_8") (pintype "bidirectional"))
      (node (ref "U8") (pin "14") (pinfunction "~{SS}_14") (pintype "bidirectional"))
    )
    (net (code "22") (name "AUX_GREEN_BOT") (class "Default")
      (node (ref "Q6") (pin "1") (pinfunction "G_1") (pintype "passive"))
      (node (ref "TO_MAIN2") (pin "5") (pinfunction "5_5") (pintype "bidirectional"))
    )
    (net (code "23") (name "AUX_GREEN_TOP") (class "Default")
      (node (ref "Q3") (pin "1") (pinfunction "G_1") (pintype "passive"))
      (node (ref "TO_MAIN2") (pin "6") (pinfunction "6_6") (pintype "bidirectional"))
    )
    (net (code "24") (name "AUX_MISO") (class "Default")
      (node (ref "TO_MAIN1") (pin "4") (pinfunction "4_4") (pintype "bidirectional"))
      (node (ref "U8") (pin "16") (pinfunction "MISO_16") (pintype "bidirectional"))
    )
    (net (code "25") (name "AUX_MOSI") (class "Default")
      (node (ref "TO_MAIN1") (pin "6") (pinfunction "6_6") (pintype "bidirectional"))
      (node (ref "U8") (pin "15") (pinfunction "MOSI_15") (pintype "bidirectional"))
    )
    (net (code "26") (name "AUX_RED_BOT") (class "Default")
      (node (ref "Q5") (pin "1") (pinfunction "G_1") (pintype "passive"))
      (node (ref "TO_MAIN2") (pin "3") (pinfunction "3_3") (pintype "bidirectional"))
    )
    (net (code "27") (name "AUX_RED_TOP") (class "Default")
      (node (ref "Q2") (pin "1") (pinfunction "G_1") (pintype "passive"))
      (node (ref "TO_MAIN2") (pin "8") (pinfunction "8_8") (pintype "bidirectional"))
    )
    (net (code "28") (name "AUX_SCLK") (class "Default")
      (node (ref "TO_MAIN1") (pin "2") (pinfunction "2_2") (pintype "bidirectional"))
      (node (ref "U8") (pin "17") (pinfunction "SCK_17") (pintype "bidirectional"))
    )
    (net (code "29") (name "BCLK") (class "Default")
      (node (ref "L6") (pin "1") (pinfunction "1_1") (pintype "passive"))
      (node (ref "U3") (pin "2") (pinfunction "BCLK_2") (pintype "bidirectional"))
    )
    (net (code "30") (name "BLUE_BOT") (class "Default")
      (node (ref "TO_AUX2") (pin "8") (pinfunction "8_8") (pintype "bidirectional"))
      (node (ref "U7") (pin "135") (pinfunction "PC24_135") (pintype "bidirectional"))
    )
    (net (code "31") (name "BLUE_TOP") (class "Default")
      (node (ref "TO_AUX2") (pin "3") (pinfunction "3_3") (pintype "bidirectional"))
      (node (ref "U7") (pin "134") (pinfunction "PC23_134") (pintype "bidirectional"))
    )
    (net (code "32") (name "CS_CC8531") (class "Default")
      (node (ref "CC_DEBUG") (pin "5") (pinfunction "5_5") (pintype "bidirectional"))
      (node (ref "U1") (pin "3") (pinfunction "CSN_3") (pintype "bidirectional"))
      (node (ref "U7") (pin "22") (pinfunction "PD9_22") (pintype "bidirectional"))
    )
    (net (code "33") (name "CS_CODEC") (class "Default")
      (node (ref "U3") (pin "9") (pinfunction "SCL/SSZ_9") (pintype "bidirectional"))
      (node (ref "U7") (pin "15") (pinfunction "PD2_15") (pintype "bidirectional"))
    )
    (net (code "34") (name "CS_SD") (class "Default")
      (node (ref "MICROSD") (pin "CD/DAT3") (pinfunction "~{CS}_CD/DAT3") (pintype "bidirectional"))
      (node (ref "U7") (pin "67") (pinfunction "PC9_67") (pintype "bidirectional"))
    )
    (net (code "35") (name "CS_TOUCH") (class "Default")
      (node (ref "TO_AUX1") (pin "7") (pinfunction "7_7") (pintype "bidirectional"))
      (node (ref "U7") (pin "26") (pinfunction "PA7_26") (pintype "bidirectional"))
    )
    (net (code "36") (name "D+_CC8531") (class "Default")
      (node (ref "R2") (pin "2") (pinfunction "2_2") (pintype "passive"))
      (node (ref "R7") (pin "2") (pinfunction "2_2") (pintype "passive"))
      (node (ref "USB1") (pin "3") (pinfunction "D+_3") (pintype "bidirectional"))
    )
    (net (code "37") (name "D+_UC") (class "Default")
      (node (ref "R42") (pin "2") (pinfunction "2_2") (pintype "passive"))
      (node (ref "U7") (pin "37") (pinfunction "DHSDP_37") (pintype "bidirectional"))
      (node (ref "USB2") (pin "3") (pinfunction "D+_3") (pintype "bidirectional"))
    )
    (net (code "38") (name "D-_CC8531") (class "Default")
      (node (ref "R1") (pin "2") (pinfunction "2_2") (pintype "passive"))
      (node (ref "USB1") (pin "2") (pinfunction "D-_2") (pintype "bidirectional"))
    )
    (net (code "39") (name "D-_UC") (class "Default")
      (node (ref "R41") (pin "2") (pinfunction "2_2") (pintype "passive"))
      (node (ref "U7") (pin "38") (pinfunction "DHSDM_38") (pintype "bidirectional"))
      (node (ref "USB2") (pin "2") (pinfunction "D-_2") (pintype "bidirectional"))
    )
    (net (code "40") (name "DIN") (class "Default")
      (node (ref "L13") (pin "1") (pinfunction "1_1") (pintype "passive"))
      (node (ref "U3") (pin "4") (pinfunction "DIN/MFP1_4") (pintype "bidirectional"))
    )
    (net (code "41") (name "DOUT") (class "Default")
      (node (ref "L11") (pin "1") (pinfunction "1_1") (pintype "passive"))
      (node (ref "U3") (pin "5") (pinfunction "DOUT/MFP2_5") (pintype "bidirectional"))
    )
    (net (code "42") (name "ERASE") (class "Default")
      (node (ref "ERASE") (pin "1") (pinfunction "1_1") (pintype "bidirectional"))
      (node (ref "U7") (pin "130") (pinfunction "PC0_130") (pintype "bidirectional"))
    )
    (net (code "43") (name "GND") (class "Default")
      (node (ref "BATTERY") (pin "-") (pinfunction "N_-") (pintype "passive"))
      (node (ref "BATTERY") (pin "X1") (pinfunction "CASE_X1") (pintype "passive"))
      (node (ref "BATTERY") (pin "X2") (pinfunction "CASE_X2") (pintype "passive"))
      (node (ref "C1") (pin "2") (pinfunction "2_2") (pintype "passive"))
      (node (ref "C10") (pin "2") (pinfunction "2_2") (pintype "passive"))
      (node (ref "C11") (pin "2") (pinfunction "2_2") (pintype "passive"))
      (node (ref "C12") (pin "2") (pinfunction "2_2") (pintype "passive"))
      (node (ref "C13") (pin "2") (pinfunction "2_2") (pintype "passive"))
      (node (ref "C14") (pin "2") (pinfunction "2_2") (pintype "passive"))
      (node (ref "C15") (pin "2") (pinfunction "2_2") (pintype "passive"))
      (node (ref "C16") (pin "2") (pinfunction "2_2") (pintype "passive"))
      (node (ref "C17") (pin "2") (pinfunction "2_2") (pintype "passive"))
      (node (ref "C18") (pin "2") (pinfunction "2_2") (pintype "passive"))
      (node (ref "C19") (pin "2") (pinfunction "2_2") (pintype "passive"))
      (node (ref "C2") (pin "2") (pinfunction "2_2") (pintype "passive"))
      (node (ref "C20") (pin "2") (pinfunction "2_2") (pintype "passive"))
      (node (ref "C21") (pin "2") (pinfunction "2_2") (pintype "passive"))
      (node (ref "C22") (pin "2") (pinfunction "2_2") (pintype "passive"))
      (node (ref "C23") (pin "2") (pinfunction "2_2") (pintype "passive"))
      (node (ref "C24") (pin "2") (pinfunction "2_2") (pintype "passive"))
      (node (ref "C27") (pin "2") (pinfunction "2_2") (pintype "passive"))
      (node (ref "C28") (pin "2") (pinfunction "2_2") (pintype "passive"))
      (node (ref "C29") (pin "2") (pinfunction "2_2") (pintype "passive"))
      (node (ref "C3") (pin "2") (pinfunction "2_2") (pintype "passive"))
      (node (ref "C30") (pin "2") (pinfunction "2_2") (pintype "passive"))
      (node (ref "C32") (pin "2") (pinfunction "2_2") (pintype "passive"))
      (node (ref "C35") (pin "2") (pinfunction "2_2") (pintype "passive"))
      (node (ref "C4") (pin "2") (pinfunction "2_2") (pintype "passive"))
      (node (ref "C43") (pin "2") (pinfunction "2_2") (pintype "passive"))
      (node (ref "C44") (pin "2") (pinfunction "2_2") (pintype "passive"))
      (node (ref "C45") (pin "2") (pinfunction "2_2") (pintype "passive"))
      (node (ref "C46") (pin "2") (pinfunction "2_2") (pintype "passive"))
      (node (ref "C47") (pin "2") (pinfunction "2_2") (pintype "passive"))
      (node (ref "C49") (pin "2") (pinfunction "2_2") (pintype "passive"))
      (node (ref "C5") (pin "2") (pinfunction "2_2") (pintype "passive"))
      (node (ref "C51") (pin "2") (pinfunction "2_2") (pintype "passive"))
      (node (ref "C52") (pin "2") (pinfunction "2_2") (pintype "passive"))
      (node (ref "C53") (pin "2") (pinfunction "2_2") (pintype "passive"))
      (node (ref "C54") (pin "2") (pinfunction "2_2") (pintype "passive"))
      (node (ref "C56") (pin "2") (pinfunction "2_2") (pintype "passive"))
      (node (ref "C57") (pin "2") (pinfunction "2_2") (pintype "passive"))
      (node (ref "C6") (pin "2") (pinfunction "2_2") (pintype "passive"))
      (node (ref "C65") (pin "2") (pinfunction "2_2") (pintype "passive"))
      (node (ref "C68") (pin "2") (pinfunction "2_2") (pintype "passive"))
      (node (ref "C7") (pin "2") (pinfunction "2_2") (pintype "passive"))
      (node (ref "C8") (pin "2") (pinfunction "2_2") (pintype "passive"))
      (node (ref "C9") (pin "2") (pinfunction "2_2") (pintype "passive"))
      (node (ref "CC_DEBUG") (pin "1") (pinfunction "1_1") (pintype "bidirectional"))
      (node (ref "JTAG") (pin "3") (pinfunction "3_3") (pintype "bidirectional"))
      (node (ref "JTAG") (pin "5") (pinfunction "5_5") (pintype "bidirectional"))
      (node (ref "JTAG") (pin "9") (pinfunction "9_9") (pintype "bidirectional"))
      (node (ref "L10") (pin "1") (pinfunction "1_1") (pintype "passive"))
      (node (ref "MICROSD") (pin "GND1") (pinfunction "GND_GND1") (pintype "bidirectional"))
      (node (ref "MICROSD") (pin "GND2") (pinfunction "GND_GND2") (pintype "bidirectional"))
      (node (ref "MICROSD") (pin "GND3") (pinfunction "GND_GND3") (pintype "bidirectional"))
      (node (ref "MICROSD") (pin "GND4") (pinfunction "GND_GND4") (pintype "bidirectional"))
      (node (ref "MICROSD") (pin "SWB") (pinfunction "SWB_SWB") (pintype "bidirectional"))
      (node (ref "MICROSD") (pin "VSS") (pinfunction "GND_VSS") (pintype "bidirectional"))
      (node (ref "POWER") (pin "C") (pinfunction "C_C") (pintype "passive"))
      (node (ref "R10") (pin "1") (pinfunction "1_1") (pintype "passive"))
      (node (ref "R17") (pin "1") (pinfunction "1_1") (pintype "passive"))
      (node (ref "R20") (pin "1") (pinfunction "1_1") (pintype "passive"))
      (node (ref "R21") (pin "1") (pinfunction "1_1") (pintype "passive"))
      (node (ref "R32") (pin "1") (pinfunction "1_1") (pintype "passive"))
      (node (ref "R4") (pin "1") (pinfunction "1_1") (pintype "passive"))
      (node (ref "R8") (pin "1") (pinfunction "1_1") (pintype "passive"))
      (node (ref "RESET") (pin "3") (pinfunction "3_3") (pintype "bidirectional"))
      (node (ref "SMA") (pin "GND1") (pinfunction "GND_GND1") (pintype "bidirectional"))
      (node (ref "SMA") (pin "GND2") (pinfunction "GND_GND2") (pintype "bidirectional"))
      (node (ref "SMA") (pin "GND3") (pinfunction "GND_GND3") (pintype "bidirectional"))
      (node (ref "SMA") (pin "GND4") (pinfunction "GND_GND4") (pintype "bidirectional"))
      (node (ref "TO_AUX1") (pin "10") (pinfunction "10_10") (pintype "bidirectional"))
      (node (ref "TO_AUX1") (pin "6") (pinfunction "6_6") (pintype "bidirectional"))
      (node (ref "TO_AUX1") (pin "8") (pinfunction "8_8") (pintype "bidirectional"))
      (node (ref "TO_AUX2") (pin "10") (pinfunction "10_10") (pintype "bidirectional"))
      (node (ref "TO_AUX2") (pin "9") (pinfunction "9_9") (pintype "bidirectional"))
      (node (ref "U1") (pin "29") (pinfunction "VBAT_29") (pintype "bidirectional"))
      (node (ref "U1") (pin "34") (pinfunction "GIO12_34") (pintype "bidirectional"))
      (node (ref "U1") (pin "35") (pinfunction "GIO13_35") (pintype "bidirectional"))
      (node (ref "U1") (pin "8") (pinfunction "GIO2_8") (pintype "bidirectional"))
      (node (ref "U1") (pin "GND") (pinfunction "GND_GND") (pintype "bidirectional"))
      (node (ref "U2") (pin "12") (pinfunction "GND_12") (pintype "bidirectional"))
      (node (ref "U2") (pin "14") (pinfunction "GND_14") (pintype "bidirectional"))
      (node (ref "U2") (pin "8") (pinfunction "GND_8") (pintype "bidirectional"))
      (node (ref "U2") (pin "9") (pinfunction "GND_9") (pintype "bidirectional"))
      (node (ref "U2") (pin "GND") (pinfunction "GND_GND") (pintype "bidirectional"))
      (node (ref "U3") (pin "28") (pinfunction "DVSS_28") (pintype "bidirectional"))
      (node (ref "U3") (pin "7") (pinfunction "IOVSS_7") (pintype "bidirectional"))
      (node (ref "U3") (pin "GND") (pinfunction "GND_GND") (pintype "bidirectional"))
      (node (ref "U5") (pin "2") (pinfunction "GND_2") (pintype "bidirectional"))
      (node (ref "U5") (pin "4") (pinfunction "GND_4") (pintype "bidirectional"))
      (node (ref "U6") (pin "1") (pinfunction "NTC_1") (pintype "bidirectional"))
      (node (ref "U6") (pin "14") (pinfunction "D1_14") (pintype "bidirectional"))
      (node (ref "U6") (pin "4") (pinfunction "D2_4") (pintype "bidirectional"))
      (node (ref "U6") (pin "GND") (pinfunction "GND_GND") (pintype "bidirectional"))
      (node (ref "U7") (pin "106") (pinfunction "GND_3_106") (pintype "bidirectional"))
      (node (ref "U7") (pin "12") (pinfunction "GND_1_12") (pintype "bidirectional"))
      (node (ref "U7") (pin "126") (pinfunction "GND_4_126") (pintype "bidirectional"))
      (node (ref "U7") (pin "33") (pinfunction "GNDPLL_33") (pintype "bidirectional"))
      (node (ref "U7") (pin "44") (pinfunction "GNDUTMI_44") (pintype "bidirectional"))
      (node (ref "U7") (pin "46") (pinfunction "JTAGSEL_46") (pintype "bidirectional"))
      (node (ref "U7") (pin "54") (pinfunction "GNDBU_54") (pintype "bidirectional"))
      (node (ref "U7") (pin "58") (pinfunction "GND_2_58") (pintype "bidirectional"))
      (node (ref "U7") (pin "74") (pinfunction "GNDANA_74") (pintype "bidirectional"))
      (node (ref "USB1") (pin "5") (pinfunction "GND_5") (pintype "bidirectional"))
      (node (ref "USB1") (pin "GND1") (pinfunction "GND_GND1") (pintype "bidirectional"))
      (node (ref "USB1") (pin "GND2") (pinfunction "GND_GND2") (pintype "bidirectional"))
      (node (ref "USB1") (pin "GND3") (pinfunction "GND_GND3") (pintype "bidirectional"))
      (node (ref "USB1") (pin "GND4") (pinfunction "GND_GND4") (pintype "bidirectional"))
      (node (ref "USB2") (pin "5") (pinfunction "GND_5") (pintype "bidirectional"))
      (node (ref "USB2") (pin "GND1") (pinfunction "GND_GND1") (pintype "bidirectional"))
      (node (ref "USB2") (pin "GND2") (pinfunction "GND_GND2") (pintype "bidirectional"))
      (node (ref "USB2") (pin "GND3") (pinfunction "GND_GND3") (pintype "bidirectional"))
      (node (ref "USB2") (pin "GND4") (pinfunction "GND_GND4") (pintype "bidirectional"))
      (node (ref "X1") (pin "2") (pinfunction "CASE_2") (pintype "passive"))
      (node (ref "X1") (pin "4") (pinfunction "CASE_4") (pintype "passive"))
      (node (ref "X3") (pin "GND-1") (pinfunction "CASE_GND-1") (pintype "passive"))
      (node (ref "X3") (pin "GND-2") (pinfunction "CASE_GND-2") (pintype "passive"))
    )
    (net (code "44") (name "GREEN_BOT") (class "Default")
      (node (ref "TO_AUX2") (pin "6") (pinfunction "6_6") (pintype "bidirectional"))
      (node (ref "U7") (pin "136") (pinfunction "PC25_136") (pintype "bidirectional"))
    )
    (net (code "45") (name "GREEN_TOP") (class "Default")
      (node (ref "TO_AUX2") (pin "5") (pinfunction "5_5") (pintype "bidirectional"))
      (node (ref "U7") (pin "133") (pinfunction "PC22_133") (pintype "bidirectional"))
    )
    (net (code "46") (name "IN_L") (class "Default")
      (node (ref "C38") (pin "1") (pinfunction "1_1") (pintype "passive"))
      (node (ref "LINE_IN") (pin "4") (pinfunction "L_4") (pintype "bidirectional"))
      (node (ref "R23") (pin "2") (pinfunction "2_2") (pintype "passive"))
    )
    (net (code "47") (name "IN_R") (class "Default")
      (node (ref "C37") (pin "1") (pinfunction "1_1") (pintype "passive"))
      (node (ref "LINE_IN") (pin "1") (pinfunction "R_1") (pintype "bidirectional"))
    )
    (net (code "48") (name "LINEIN_SENSE") (class "Default")
      (node (ref "LINE_IN") (pin "3") (pinfunction "L_SW_3") (pintype "bidirectional"))
      (node (ref "R22") (pin "1") (pinfunction "1_1") (pintype "passive"))
      (node (ref "U7") (pin "101") (pinfunction "PC19_101") (pintype "bidirectional"))
    )
    (net (code "49") (name "LINE_L") (class "Default")
      (node (ref "R27") (pin "1") (pinfunction "1_1") (pintype "passive"))
      (node (ref "U3") (pin "22") (pinfunction "LOL_22") (pintype "bidirectional"))
    )
    (net (code "50") (name "LINE_R") (class "Default")
      (node (ref "R29") (pin "1") (pinfunction "1_1") (pintype "passive"))
      (node (ref "U3") (pin "23") (pinfunction "LOR_23") (pintype "bidirectional"))
    )
    (net (code "51") (name "LNA_EN") (class "Default")
      (node (ref "U1") (pin "38") (pinfunction "XLNAEN_38") (pintype "bidirectional"))
      (node (ref "U2") (pin "6") (pinfunction "EN_6") (pintype "bidirectional"))
    )
    (net (code "52") (name "MCLK") (class "Default")
      (node (ref "L5") (pin "1") (pinfunction "1_1") (pintype "passive"))
      (node (ref "U3") (pin "1") (pinfunction "MCLK_1") (pintype "bidirectional"))
    )
    (net (code "53") (name "MISO") (class "Default")
      (node (ref "CC_DEBUG") (pin "10") (pinfunction "10_10") (pintype "bidirectional"))
      (node (ref "MICROSD") (pin "DAT0") (pinfunction "MISO_DAT0") (pintype "bidirectional"))
      (node (ref "TO_AUX1") (pin "3") (pinfunction "3_3") (pintype "bidirectional"))
      (node (ref "U1") (pin "6") (pinfunction "MISO_6") (pintype "bidirectional"))
      (node (ref "U3") (pin "11") (pinfunction "MISO/MFP4_11") (pintype "bidirectional"))
      (node (ref "U7") (pin "108") (pinfunction "PA25_108") (pintype "bidirectional"))
    )
    (net (code "54") (name "MOSI") (class "Default")
      (node (ref "CC_DEBUG") (pin "8") (pinfunction "8_8") (pintype "bidirectional"))
      (node (ref "MICROSD") (pin "CMD") (pinfunction "MOSI_CMD") (pintype "bidirectional"))
      (node (ref "TO_AUX1") (pin "5") (pinfunction "5_5") (pintype "bidirectional"))
      (node (ref "U1") (pin "5") (pinfunction "MOSI_5") (pintype "bidirectional"))
      (node (ref "U3") (pin "10") (pinfunction "SDA/MOSI_10") (pintype "bidirectional"))
      (node (ref "U7") (pin "109") (pinfunction "PA26_109") (pintype "bidirectional"))
    )
    (net (code "55") (name "Net-(AVR-PadA)") (class "Default")
      (node (ref "AVR") (pin "A") (pinfunction "A_A") (pintype "passive"))
      (node (ref "R44") (pin "1") (pinfunction "1_1") (pintype "passive"))
    )
    (net (code "56") (name "Net-(BATTERY-P)") (class "Default")
      (node (ref "BATTERY") (pin "+") (pinfunction "P_+") (pintype "passive"))
      (node (ref "Q1") (pin "2") (pinfunction "S_2") (pintype "passive"))
      (node (ref "U6") (pin "9") (pinfunction "BAT_9") (pintype "bidirectional"))
    )
    (net (code "57") (name "Net-(C25-Pad1)") (class "Default")
      (node (ref "C25") (pin "1") (pinfunction "1_1") (pintype "passive"))
      (node (ref "L8") (pin "2") (pinfunction "2_2") (pintype "passive"))
    )
    (net (code "58") (name "Net-(C25-Pad2)") (class "Default")
      (node (ref "C25") (pin "2") (pinfunction "2_2") (pintype "passive"))
      (node (ref "C26") (pin "1") (pinfunction "1_1") (pintype "passive"))
      (node (ref "C28") (pin "1") (pinfunction "1_1") (pintype "passive"))
      (node (ref "L10") (pin "2") (pinfunction "2_2") (pintype "passive"))
    )
    (net (code "59") (name "Net-(C26-Pad2)") (class "Default")
      (node (ref "C26") (pin "2") (pinfunction "2_2") (pintype "passive"))
      (node (ref "SMA") (pin "SIG") (pinfunction "SIG_SIG") (pintype "bidirectional"))
    )
    (net (code "60") (name "Net-(C27-Pad1)") (class "Default")
      (node (ref "C27") (pin "1") (pinfunction "1_1") (pintype "passive"))
      (node (ref "L7") (pin "2") (pinfunction "2_2") (pintype "passive"))
      (node (ref "L8") (pin "1") (pinfunction "1_1") (pintype "passive"))
    )
    (net (code "61") (name "Net-(C54-Pad1)") (class "Default")
      (node (ref "C54") (pin "1") (pinfunction "1_1") (pintype "passive"))
      (node (ref "R19") (pin "1") (pinfunction "1_1") (pintype "passive"))
    )
    (net (code "62") (name "Net-(C57-Pad1)") (class "Default")
      (node (ref "C57") (pin "1") (pinfunction "1_1") (pintype "passive"))
      (node (ref "L19") (pin "1") (pinfunction "1_1") (pintype "passive"))
      (node (ref "TO_AUX2") (pin "1") (pinfunction "1_1") (pintype "bidirectional"))
      (node (ref "TO_AUX2") (pin "2") (pinfunction "2_2") (pintype "bidirectional"))
    )
    (net (code "63") (name "Net-(C65-Pad1)") (class "Default")
      (node (ref "C65") (pin "1") (pinfunction "1_1") (pintype "passive"))
      (node (ref "L18") (pin "1") (pinfunction "1_1") (pintype "passive"))
      (node (ref "TO_AUX1") (pin "2") (pinfunction "2_2") (pintype "bidirectional"))
      (node (ref "TO_AUX1") (pin "4") (pinfunction "4_4") (pintype "bidirectional"))
    )
    (net (code "64") (name "Net-(CC8531-PadC)") (class "Default")
      (node (ref "CC8531") (pin "C") (pinfunction "C_C") (pintype "passive"))
      (node (ref "R5") (pin "2") (pinfunction "2_2") (pintype "passive"))
    )
    (net (code "65") (name "Net-(CC_DEBUG-Pad9)") (class "Default")
      (node (ref "CC_DEBUG") (pin "9") (pinfunction "9_9") (pintype "bidirectional"))
      (node (ref "EXT") (pin "1") (pinfunction "1_1") (pintype "passive"))
    )
    (net (code "66") (name "Net-(CHARGE-PadA)") (class "Default")
      (node (ref "CHARGE") (pin "A") (pinfunction "A_A") (pintype "passive"))
      (node (ref "R18") (pin "1") (pinfunction "1_1") (pintype "passive"))
    )
    (net (code "67") (name "Net-(POWER-PadA)") (class "Default")
      (node (ref "POWER") (pin "A") (pinfunction "A_A") (pintype "passive"))
      (node (ref "R3") (pin "1") (pinfunction "1_1") (pintype "passive"))
    )
    (net (code "68") (name "Net-(Q1-D)") (class "Default")
      (node (ref "C52") (pin "1") (pinfunction "1_1") (pintype "passive"))
      (node (ref "F1") (pin "1") (pinfunction "1_1") (pintype "passive"))
      (node (ref "L17") (pin "2") (pinfunction "2_2") (pintype "passive"))
      (node (ref "Q1") (pin "3") (pinfunction "D_3") (pintype "passive"))
      (node (ref "U6") (pin "10") (pinfunction "VOUT_10") (pintype "bidirectional"))
      (node (ref "U6") (pin "3") (pinfunction "VOUTS_3") (pintype "bidirectional"))
    )
    (net (code "69") (name "Net-(Q1-G)") (class "Default")
      (node (ref "Q1") (pin "1") (pinfunction "G_1") (pintype "passive"))
      (node (ref "U6") (pin "8") (pinfunction "GATE_8") (pintype "bidirectional"))
    )
    (net (code "70") (name "Net-(Q2-D)") (class "Default")
      (node (ref "LED_UL") (pin "1") (pinfunction "KR_1") (pintype "passive"))
      (node (ref "LED_UL") (pin "1-2") (pinfunction "KR_1-2") (pintype "passive"))
      (node (ref "LED_UR") (pin "1") (pinfunction "KR_1") (pintype "passive"))
      (node (ref "LED_UR") (pin "1-2") (pinfunction "KR_1-2") (pintype "passive"))
      (node (ref "Q2") (pin "3") (pinfunction "D_3") (pintype "passive"))
    )
    (net (code "71") (name "Net-(Q3-D)") (class "Default")
      (node (ref "LED_UL") (pin "4") (pinfunction "KG_4") (pintype "passive"))
      (node (ref "LED_UL") (pin "4-2") (pinfunction "KG_4-2") (pintype "passive"))
      (node (ref "LED_UR") (pin "4") (pinfunction "KG_4") (pintype "passive"))
      (node (ref "LED_UR") (pin "4-2") (pinfunction "KG_4-2") (pintype "passive"))
      (node (ref "Q3") (pin "3") (pinfunction "D_3") (pintype "passive"))
    )
    (net (code "72") (name "Net-(Q4-D)") (class "Default")
      (node (ref "LED_UL") (pin "3") (pinfunction "KB_3") (pintype "passive"))
      (node (ref "LED_UL") (pin "3-2") (pinfunction "KB_3-2") (pintype "passive"))
      (node (ref "LED_UR") (pin "3") (pinfunction "KB_3") (pintype "passive"))
      (node (ref "LED_UR") (pin "3-2") (pinfunction "KB_3-2") (pintype "passive"))
      (node (ref "Q4") (pin "3") (pinfunction "D_3") (pintype "passive"))
    )
    (net (code "73") (name "Net-(Q5-D)") (class "Default")
      (node (ref "LED_LL") (pin "1") (pinfunction "KR_1") (pintype "passive"))
      (node (ref "LED_LL") (pin "1-2") (pinfunction "KR_1-2") (pintype "passive"))
      (node (ref "LED_LR") (pin "1") (pinfunction "KR_1") (pintype "passive"))
      (node (ref "LED_LR") (pin "1-2") (pinfunction "KR_1-2") (pintype "passive"))
      (node (ref "Q5") (pin "3") (pinfunction "D_3") (pintype "passive"))
    )
    (net (code "74") (name "Net-(Q6-D)") (class "Default")
      (node (ref "LED_LL") (pin "4") (pinfunction "KG_4") (pintype "passive"))
      (node (ref "LED_LL") (pin "4-2") (pinfunction "KG_4-2") (pintype "passive"))
      (node (ref "LED_LR") (pin "4") (pinfunction "KG_4") (pintype "passive"))
      (node (ref "LED_LR") (pin "4-2") (pinfunction "KG_4-2") (pintype "passive"))
      (node (ref "Q6") (pin "3") (pinfunction "D_3") (pintype "passive"))
    )
    (net (code "75") (name "Net-(Q7-D)") (class "Default")
      (node (ref "LED_LL") (pin "3") (pinfunction "KB_3") (pintype "passive"))
      (node (ref "LED_LL") (pin "3-2") (pinfunction "KB_3-2") (pintype "passive"))
      (node (ref "LED_LR") (pin "3") (pinfunction "KB_3") (pintype "passive"))
      (node (ref "LED_LR") (pin "3-2") (pinfunction "KB_3-2") (pintype "passive"))
      (node (ref "Q7") (pin "3") (pinfunction "D_3") (pintype "passive"))
    )
    (net (code "76") (name "Net-(R13-Pad2)") (class "Default")
      (node (ref "R13") (pin "2") (pinfunction "2_2") (pintype "passive"))
      (node (ref "R27") (pin "2") (pinfunction "2_2") (pintype "passive"))
      (node (ref "R28") (pin "2") (pinfunction "2_2") (pintype "passive"))
    )
    (net (code "77") (name "Net-(R16-Pad2)") (class "Default")
      (node (ref "R16") (pin "2") (pinfunction "2_2") (pintype "passive"))
      (node (ref "R29") (pin "2") (pinfunction "2_2") (pintype "passive"))
      (node (ref "R30") (pin "2") (pinfunction "2_2") (pintype "passive"))
    )
    (net (code "78") (name "Net-(R26-Pad2)") (class "Default")
      (node (ref "R26") (pin "2") (pinfunction "2_2") (pintype "passive"))
      (node (ref "SW1") (pin "P$1") (pinfunction "P$1_P$1") (pintype "bidirectional"))
    )
    (net (code "79") (name "Net-(R33-Pad2)") (class "Default")
      (node (ref "R33") (pin "2") (pinfunction "2_2") (pintype "passive"))
      (node (ref "SW4") (pin "P$1") (pinfunction "P$1_P$1") (pintype "bidirectional"))
    )
    (net (code "80") (name "Net-(R34-Pad2)") (class "Default")
      (node (ref "R34") (pin "2") (pinfunction "2_2") (pintype "passive"))
      (node (ref "SW5") (pin "P$1") (pinfunction "P$1_P$1") (pintype "bidirectional"))
    )
    (net (code "81") (name "Net-(R35-Pad2)") (class "Default")
      (node (ref "R35") (pin "2") (pinfunction "2_2") (pintype "passive"))
      (node (ref "SW6") (pin "P$1") (pinfunction "P$1_P$1") (pintype "bidirectional"))
    )
    (net (code "82") (name "Net-(R37-Pad2)") (class "Default")
      (node (ref "R37") (pin "2") (pinfunction "2_2") (pintype "passive"))
      (node (ref "SW7") (pin "P$1") (pinfunction "P$1_P$1") (pintype "bidirectional"))
    )
    (net (code "83") (name "Net-(R38-Pad2)") (class "Default")
      (node (ref "R38") (pin "2") (pinfunction "2_2") (pintype "passive"))
      (node (ref "SW8") (pin "P$1") (pinfunction "P$1_P$1") (pintype "bidirectional"))
    )
    (net (code "84") (name "Net-(R39-Pad2)") (class "Default")
      (node (ref "R39") (pin "2") (pinfunction "2_2") (pintype "passive"))
      (node (ref "SW9") (pin "P$1") (pinfunction "P$1_P$1") (pintype "bidirectional"))
    )
    (net (code "85") (name "Net-(R40-Pad2)") (class "Default")
      (node (ref "R40") (pin "2") (pinfunction "2_2") (pintype "passive"))
      (node (ref "SW10") (pin "P$1") (pinfunction "P$1_P$1") (pintype "bidirectional"))
    )
    (net (code "86") (name "Net-(U1-AD0{slash}GIO7)") (class "Default")
      (node (ref "L11") (pin "2") (pinfunction "2_2") (pintype "passive"))
      (node (ref "U1") (pin "16") (pinfunction "AD0/GIO7_16") (pintype "bidirectional"))
    )
    (net (code "87") (name "Net-(U1-AD1{slash}GIO8)") (class "Default")
      (node (ref "L13") (pin "2") (pinfunction "2_2") (pintype "passive"))
      (node (ref "U1") (pin "17") (pinfunction "AD1/GIO8_17") (pintype "bidirectional"))
    )
    (net (code "88") (name "Net-(U1-BCLK{slash}GIO5)") (class "Default")
      (node (ref "L6") (pin "2") (pinfunction "2_2") (pintype "passive"))
      (node (ref "U1") (pin "14") (pinfunction "BCLK/GIO5_14") (pintype "bidirectional"))
    )
    (net (code "89") (name "Net-(U1-DCPL)") (class "Default")
      (node (ref "C23") (pin "1") (pinfunction "1_1") (pintype "passive"))
      (node (ref "U1") (pin "39") (pinfunction "DCPL_39") (pintype "bidirectional"))
    )
    (net (code "90") (name "Net-(U1-GIO3)") (class "Default")
      (node (ref "R5") (pin "1") (pinfunction "1_1") (pintype "passive"))
      (node (ref "U1") (pin "9") (pinfunction "GIO3_9") (pintype "bidirectional"))
    )
    (net (code "91") (name "Net-(U1-MCLK{slash}GIO4)") (class "Default")
      (node (ref "L5") (pin "2") (pinfunction "2_2") (pintype "passive"))
      (node (ref "U1") (pin "13") (pinfunction "MCLK/GIO4_13") (pintype "bidirectional"))
    )
    (net (code "92") (name "Net-(U1-RBIAS)") (class "Default")
      (node (ref "R4") (pin "2") (pinfunction "2_2") (pintype "passive"))
      (node (ref "U1") (pin "30") (pinfunction "RBIAS_30") (pintype "bidirectional"))
    )
    (net (code "93") (name "Net-(U1-RSTN)") (class "Default")
      (node (ref "L4") (pin "1") (pinfunction "1_1") (pintype "passive"))
      (node (ref "U1") (pin "11") (pinfunction "RSTN_11") (pintype "bidirectional"))
    )
    (net (code "94") (name "Net-(U1-USBN)") (class "Default")
      (node (ref "C14") (pin "1") (pinfunction "1_1") (pintype "passive"))
      (node (ref "R1") (pin "1") (pinfunction "1_1") (pintype "passive"))
      (node (ref "U1") (pin "1") (pinfunction "USBN_1") (pintype "bidirectional"))
    )
    (net (code "95") (name "Net-(U1-USBP)") (class "Default")
      (node (ref "C13") (pin "1") (pinfunction "1_1") (pintype "passive"))
      (node (ref "R2") (pin "1") (pinfunction "1_1") (pintype "passive"))
      (node (ref "U1") (pin "2") (pinfunction "USBP_2") (pintype "bidirectional"))
    )
    (net (code "96") (name "Net-(U1-WCLK{slash}GIO6)") (class "Default")
      (node (ref "L9") (pin "2") (pinfunction "2_2") (pintype "passive"))
      (node (ref "U1") (pin "15") (pinfunction "WCLK/GIO6_15") (pintype "bidirectional"))
    )
    (net (code "97") (name "Net-(U1-X0)") (class "Default")
      (node (ref "C24") (pin "1") (pinfunction "1_1") (pintype "passive"))
      (node (ref "U1") (pin "22") (pinfunction "X0_22") (pintype "bidirectional"))
      (node (ref "X1") (pin "3") (pinfunction "2_3") (pintype "passive"))
    )
    (net (code "98") (name "Net-(U1-X1)") (class "Default")
      (node (ref "C29") (pin "1") (pinfunction "1_1") (pintype "passive"))
      (node (ref "U1") (pin "21") (pinfunction "X1_21") (pintype "bidirectional"))
      (node (ref "X1") (pin "1") (pinfunction "1_1") (pintype "passive"))
    )
    (net (code "99") (name "Net-(U1-XPAEN)") (class "Default")
      (node (ref "L12") (pin "1") (pinfunction "1_1") (pintype "passive"))
      (node (ref "U1") (pin "36") (pinfunction "XPAEN_36") (pintype "bidirectional"))
    )
    (net (code "100") (name "Net-(U2-ANT)") (class "Default")
      (node (ref "L7") (pin "1") (pinfunction "1_1") (pintype "passive"))
      (node (ref "U2") (pin "11") (pinfunction "ANT_11") (pintype "bidirectional"))
    )
    (net (code "101") (name "Net-(U2-BIAS)") (class "Default")
      (node (ref "R8") (pin "2") (pinfunction "2_2") (pintype "passive"))
      (node (ref "U2") (pin "15") (pinfunction "BIAS_15") (pintype "bidirectional"))
    )
    (net (code "102") (name "Net-(U2-HGM)") (class "Default")
      (node (ref "R9") (pin "1") (pinfunction "1_1") (pintype "passive"))
      (node (ref "U2") (pin "7") (pinfunction "HGM_7") (pintype "bidirectional"))
    )
    (net (code "103") (name "Net-(U3-AVDD)") (class "Default")
      (node (ref "C48") (pin "1") (pinfunction "1_1") (pintype "passive"))
      (node (ref "U3") (pin "24") (pinfunction "AVDD_24") (pintype "bidirectional"))
    )
    (net (code "104") (name "Net-(U3-DVDD)") (class "Default")
      (node (ref "C49") (pin "1") (pinfunction "1_1") (pintype "passive"))
      (node (ref "U3") (pin "29") (pinfunction "DVDD_29") (pintype "bidirectional"))
    )
    (net (code "105") (name "Net-(U3-IN1_L)") (class "Default")
      (node (ref "C38") (pin "2") (pinfunction "2_2") (pintype "passive"))
      (node (ref "U3") (pin "13") (pinfunction "IN1_L_13") (pintype "bidirectional"))
    )
    (net (code "106") (name "Net-(U3-IN1_R)") (class "Default")
      (node (ref "C37") (pin "2") (pinfunction "2_2") (pintype "passive"))
      (node (ref "U3") (pin "14") (pinfunction "IN1_R_14") (pintype "bidirectional"))
    )
    (net (code "107") (name "Net-(U3-REF)") (class "Default")
      (node (ref "C50") (pin "1") (pinfunction "1_1") (pintype "passive"))
      (node (ref "U3") (pin "18") (pinfunction "REF_18") (pintype "bidirectional"))
    )
    (net (code "108") (name "Net-(U5-VIN)") (class "Default")
      (node (ref "F1") (pin "2") (pinfunction "2_2") (pintype "passive"))
      (node (ref "U5") (pin "1") (pinfunction "VIN_1") (pintype "bidirectional"))
    )
    (net (code "109") (name "Net-(U6-CLRPROG)") (class "Default")
      (node (ref "R19") (pin "2") (pinfunction "2_2") (pintype "passive"))
      (node (ref "R20") (pin "2") (pinfunction "2_2") (pintype "passive"))
      (node (ref "U6") (pin "2") (pinfunction "CLRPROG_2") (pintype "bidirectional"))
    )
    (net (code "110") (name "Net-(U6-C{slash}X)") (class "Default")
      (node (ref "R21") (pin "2") (pinfunction "2_2") (pintype "passive"))
      (node (ref "U6") (pin "5") (pinfunction "C/X_5") (pintype "bidirectional"))
      (node (ref "U6") (pin "6") (pinfunction "PROG_6") (pintype "bidirectional"))
    )
    (net (code "111") (name "Net-(U6-SW)") (class "Default")
      (node (ref "L17") (pin "1") (pinfunction "1_1") (pintype "passive"))
      (node (ref "U6") (pin "12") (pinfunction "SW_12") (pintype "bidirectional"))
    )
    (net (code "112") (name "Net-(U6-~{CHRG})") (class "Default")
      (node (ref "CHARGE") (pin "C") (pinfunction "C_C") (pintype "passive"))
      (node (ref "U6") (pin "7") (pinfunction "~{CHRG}_7") (pintype "bidirectional"))
    )
    (net (code "113") (name "Net-(U7F-DFSDM)") (class "Default")
      (node (ref "R41") (pin "1") (pinfunction "1_1") (pintype "passive"))
      (node (ref "U7") (pin "43") (pinfunction "DFSDM_43") (pintype "bidirectional"))
    )
    (net (code "114") (name "Net-(U7F-DFSDP)") (class "Default")
      (node (ref "R42") (pin "1") (pinfunction "1_1") (pintype "passive"))
      (node (ref "U7") (pin "42") (pinfunction "DFSDP_42") (pintype "bidirectional"))
    )
    (net (code "115") (name "Net-(U7F-FWUP)") (class "Default")
      (node (ref "R43") (pin "2") (pinfunction "2_2") (pintype "passive"))
      (node (ref "U7") (pin "53") (pinfunction "FWUP_53") (pintype "bidirectional"))
    )
    (net (code "116") (name "Net-(U7F-VBG)") (class "Default")
      (node (ref "C68") (pin "1") (pinfunction "1_1") (pintype "passive"))
      (node (ref "R32") (pin "2") (pinfunction "2_2") (pintype "passive"))
      (node (ref "U7") (pin "40") (pinfunction "VBG_40") (pintype "bidirectional"))
    )
    (net (code "117") (name "Net-(U7F-XIN)") (class "Default")
      (node (ref "C30") (pin "1") (pinfunction "1_1") (pintype "passive"))
      (node (ref "U7") (pin "36") (pinfunction "XIN_36") (pintype "bidirectional"))
      (node (ref "X3") (pin "X2") (pinfunction "2_X2") (pintype "passive"))
    )
    (net (code "118") (name "Net-(U7F-XOUT)") (class "Default")
      (node (ref "C56") (pin "1") (pinfunction "1_1") (pintype "passive"))
      (node (ref "U7") (pin "35") (pinfunction "XOUT_35") (pintype "bidirectional"))
      (node (ref "X3") (pin "X1") (pinfunction "1_X1") (pintype "passive"))
    )
    (net (code "119") (name "Net-(U8-SNS3)") (class "Default")
      (node (ref "C58") (pin "1") (pinfunction "1_1") (pintype "passive"))
      (node (ref "U8") (pin "8") (pinfunction "SNS3_8") (pintype "bidirectional"))
    )
    (net (code "120") (name "Net-(U8-SNS3K)") (class "Default")
      (node (ref "C58") (pin "2") (pinfunction "2_2") (pintype "passive"))
      (node (ref "R33") (pin "1") (pinfunction "1_1") (pintype "passive"))
      (node (ref "U8") (pin "9") (pinfunction "SNS3K_9") (pintype "bidirectional"))
    )
    (net (code "121") (name "Net-(U8-SNS4)") (class "Default")
      (node (ref "C59") (pin "1") (pinfunction "1_1") (pintype "passive"))
      (node (ref "U8") (pin "10") (pinfunction "SNS4_10") (pintype "bidirectional"))
    )
    (net (code "122") (name "Net-(U8-SNS4K)") (class "Default")
      (node (ref "C59") (pin "2") (pinfunction "2_2") (pintype "passive"))
      (node (ref "R34") (pin "1") (pinfunction "1_1") (pintype "passive"))
      (node (ref "U8") (pin "11") (pinfunction "SNS4K_11") (pintype "bidirectional"))
    )
    (net (code "123") (name "Net-(U8-SNS5)") (class "Default")
      (node (ref "C60") (pin "1") (pinfunction "1_1") (pintype "passive"))
      (node (ref "U8") (pin "12") (pinfunction "SNS5_12") (pintype "bidirectional"))
    )
    (net (code "124") (name "Net-(U8-SNS5K)") (class "Default")
      (node (ref "C60") (pin "2") (pinfunction "2_2") (pintype "passive"))
      (node (ref "R35") (pin "1") (pinfunction "1_1") (pintype "passive"))
      (node (ref "U8") (pin "13") (pinfunction "SNS5K_13") (pintype "bidirectional"))
    )
    (net (code "125") (name "Net-(U8-SNS6)") (class "Default")
      (node (ref "C61") (pin "1") (pinfunction "1_1") (pintype "passive"))
      (node (ref "U8") (pin "20") (pinfunction "SNS6_20") (pintype "bidirectional"))
    )
    (net (code "126") (name "Net-(U8-SNS6K)") (class "Default")
      (node (ref "C61") (pin "2") (pinfunction "2_2") (pintype "passive"))
      (node (ref "R37") (pin "1") (pinfunction "1_1") (pintype "passive"))
      (node (ref "U8") (pin "19") (pinfunction "SNS6K_19") (pintype "bidirectional"))
    )
    (net (code "127") (name "Net-(U8-SNS7K{slash}DETECT0)") (class "Default")
      (node (ref "C62") (pin "2") (pinfunction "2_2") (pintype "passive"))
      (node (ref "R38") (pin "1") (pinfunction "1_1") (pintype "passive"))
      (node (ref "U8") (pin "22") (pinfunction "SNS7K/DETECT0_22") (pintype "bidirectional"))
    )
    (net (code "128") (name "Net-(U8-SNS7{slash}DETECT1)") (class "Default")
      (node (ref "C62") (pin "1") (pinfunction "1_1") (pintype "passive"))
      (node (ref "U8") (pin "23") (pinfunction "SNS7/DETECT1_23") (pintype "bidirectional"))
    )
    (net (code "129") (name "Net-(U8-SNS8K{slash}DETECT3)") (class "Default")
      (node (ref "C66") (pin "2") (pinfunction "2_2") (pintype "passive"))
      (node (ref "R39") (pin "1") (pinfunction "1_1") (pintype "passive"))
      (node (ref "U8") (pin "25") (pinfunction "SNS8K/DETECT3_25") (pintype "bidirectional"))
    )
    (net (code "130") (name "Net-(U8-SNS8{slash}DETECT2)") (class "Default")
      (node (ref "C66") (pin "1") (pinfunction "1_1") (pintype "passive"))
      (node (ref "U8") (pin "24") (pinfunction "SNS8/DETECT2_24") (pintype "bidirectional"))
    )
    (net (code "131") (name "Net-(U8-SNS9K{slash}DETECT5)") (class "Default")
      (node (ref "C67") (pin "2") (pinfunction "2_2") (pintype "passive"))
      (node (ref "R40") (pin "1") (pinfunction "1_1") (pintype "passive"))
      (node (ref "U8") (pin "27") (pinfunction "SNS9K/DETECT5_27") (pintype "bidirectional"))
    )
    (net (code "132") (name "Net-(U8-SNS9{slash}DETECT4)") (class "Default")
      (node (ref "C67") (pin "1") (pinfunction "1_1") (pintype "passive"))
      (node (ref "U8") (pin "26") (pinfunction "SNS9/DETECT4_26") (pintype "bidirectional"))
    )
    (net (code "133") (name "Net-(U8-SNS10K{slash}SYNC)") (class "Default")
      (node (ref "C55") (pin "2") (pinfunction "2_2") (pintype "passive"))
      (node (ref "R26") (pin "1") (pinfunction "1_1") (pintype "passive"))
      (node (ref "U8") (pin "31") (pinfunction "SNS10K/SYNC_31") (pintype "bidirectional"))
    )
    (net (code "134") (name "Net-(U8-SNS10{slash}DETECT16)") (class "Default")
      (node (ref "C55") (pin "1") (pinfunction "1_1") (pintype "passive"))
      (node (ref "U8") (pin "30") (pinfunction "SNS10/DETECT16_30") (pintype "bidirectional"))
    )
    (net (code "135") (name "Net-(U8-~{RESET})") (class "Default")
      (node (ref "R36") (pin "1") (pinfunction "1_1") (pintype "passive"))
      (node (ref "U8") (pin "29") (pinfunction "~{RESET}_29") (pintype "bidirectional"))
    )
    (net (code "136") (name "Net-(U9-BYPASS)") (class "Default")
      (node (ref "C33") (pin "1") (pinfunction "1_1") (pintype "passive"))
      (node (ref "U9") (pin "1") (pinfunction "BYPASS_1") (pintype "bidirectional"))
    )
    (net (code "137") (name "Net-(U9-INA)") (class "Default")
      (node (ref "R12") (pin "2") (pinfunction "2_2") (pintype "passive"))
      (node (ref "R13") (pin "1") (pinfunction "1_1") (pintype "passive"))
      (node (ref "U9") (pin "8") (pinfunction "INA_8") (pintype "bidirectional"))
    )
    (net (code "138") (name "Net-(U9-INB)") (class "Default")
      (node (ref "R15") (pin "2") (pinfunction "2_2") (pintype "passive"))
      (node (ref "R16") (pin "1") (pinfunction "1_1") (pintype "passive"))
      (node (ref "U9") (pin "4") (pinfunction "INB_4") (pintype "bidirectional"))
    )
    (net (code "139") (name "Net-(U9-OUTB)") (class "Default")
      (node (ref "C39") (pin "1") (pinfunction "1_1") (pintype "passive"))
      (node (ref "R15") (pin "1") (pinfunction "1_1") (pintype "passive"))
      (node (ref "U9") (pin "5") (pinfunction "OUTB_5") (pintype "bidirectional"))
    )
    (net (code "140") (name "Net-(U9-SHUTDOWN)") (class "Default")
      (node (ref "R31") (pin "1") (pinfunction "1_1") (pintype "passive"))
      (node (ref "U9") (pin "3") (pinfunction "SHUTDOWN_3") (pintype "bidirectional"))
    )
    (net (code "141") (name "OUT_L") (class "Default")
      (node (ref "C36") (pin "2") (pinfunction "2_2") (pintype "passive"))
      (node (ref "PHONE_OUT") (pin "4") (pinfunction "L_4") (pintype "bidirectional"))
      (node (ref "R25") (pin "2") (pinfunction "2_2") (pintype "passive"))
    )
    (net (code "142") (name "OUT_R") (class "Default")
      (node (ref "C39") (pin "2") (pinfunction "2_2") (pintype "passive"))
      (node (ref "PHONE_OUT") (pin "1") (pinfunction "R_1") (pintype "bidirectional"))
    )
    (net (code "143") (name "PA_EN") (class "Default")
      (node (ref "L12") (pin "2") (pinfunction "2_2") (pintype "passive"))
      (node (ref "R10") (pin "2") (pinfunction "2_2") (pintype "passive"))
      (node (ref "U2") (pin "5") (pinfunction "PAEN_5") (pintype "bidirectional"))
    )
    (net (code "144") (name "PHONE_L") (class "Default")
      (node (ref "R28") (pin "1") (pinfunction "1_1") (pintype "passive"))
      (node (ref "U3") (pin "25") (pinfunction "HPL_25") (pintype "bidirectional"))
    )
    (net (code "145") (name "PHONE_R") (class "Default")
      (node (ref "R30") (pin "1") (pinfunction "1_1") (pintype "passive"))
      (node (ref "U3") (pin "27") (pinfunction "HPR_27") (pintype "bidirectional"))
    )
    (net (code "146") (name "PHONE_SENSE") (class "Default")
      (node (ref "PHONE_OUT") (pin "3") (pinfunction "L_SW_3") (pintype "bidirectional"))
      (node (ref "R24") (pin "1") (pinfunction "1_1") (pintype "passive"))
      (node (ref "U7") (pin "140") (pinfunction "PB14_140") (pintype "bidirectional"))
    )
    (net (code "147") (name "RED_BOT") (class "Default")
      (node (ref "TO_AUX2") (pin "4") (pinfunction "4_4") (pintype "bidirectional"))
      (node (ref "U7") (pin "139") (pinfunction "PC28_139") (pintype "bidirectional"))
    )
    (net (code "148") (name "RED_TOP") (class "Default")
      (node (ref "TO_AUX2") (pin "7") (pinfunction "7_7") (pintype "bidirectional"))
      (node (ref "U7") (pin "132") (pinfunction "PC21_132") (pintype "bidirectional"))
    )
    (net (code "149") (name "RESET_CC8531") (class "Default")
      (node (ref "CC_DEBUG") (pin "7") (pinfunction "7_7") (pintype "bidirectional"))
      (node (ref "L4") (pin "2") (pinfunction "2_2") (pintype "passive"))
      (node (ref "U7") (pin "20") (pinfunction "PD7_20") (pintype "bidirectional"))
    )
    (net (code "150") (name "RESET_CODEC") (class "Default")
      (node (ref "U3") (pin "31") (pinfunction "~{RESET}_31") (pintype "bidirectional"))
      (node (ref "U7") (pin "16") (pinfunction "PD3_16") (pintype "bidirectional"))
    )
    (net (code "151") (name "RF_N") (class "Default")
      (node (ref "U1") (pin "25") (pinfunction "RF_N_25") (pintype "bidirectional"))
      (node (ref "U2") (pin "2") (pinfunction "RF_N_2") (pintype "bidirectional"))
    )
    (net (code "152") (name "RF_P") (class "Default")
      (node (ref "U1") (pin "24") (pinfunction "RF_P_24") (pintype "bidirectional"))
      (node (ref "U2") (pin "4") (pinfunction "RF_P_4") (pintype "bidirectional"))
    )
    (net (code "153") (name "RX") (class "Default")
      (node (ref "U7") (pin "27") (pinfunction "PA8_27") (pintype "bidirectional"))
    )
    (net (code "154") (name "SCLK") (class "Default")
      (node (ref "CC_DEBUG") (pin "6") (pinfunction "6_6") (pintype "bidirectional"))
      (node (ref "MICROSD") (pin "CLK") (pinfunction "SCLK_CLK") (pintype "bidirectional"))
      (node (ref "TO_AUX1") (pin "1") (pinfunction "1_1") (pintype "bidirectional"))
      (node (ref "U1") (pin "4") (pinfunction "SCLK_4") (pintype "bidirectional"))
      (node (ref "U3") (pin "8") (pinfunction "SCLK/MFP3_8") (pintype "bidirectional"))
      (node (ref "U7") (pin "110") (pinfunction "PA27_110") (pintype "bidirectional"))
    )
    (net (code "155") (name "TCK") (class "Default")
      (node (ref "JTAG") (pin "4") (pinfunction "4_4") (pintype "bidirectional"))
      (node (ref "R14") (pin "1") (pinfunction "1_1") (pintype "passive"))
      (node (ref "U7") (pin "28") (pinfunction "PB28_28") (pintype "bidirectional"))
    )
    (net (code "156") (name "TDI") (class "Default")
      (node (ref "JTAG") (pin "8") (pinfunction "8_8") (pintype "bidirectional"))
      (node (ref "R45") (pin "1") (pinfunction "1_1") (pintype "passive"))
      (node (ref "U7") (pin "29") (pinfunction "PB29_29") (pintype "bidirectional"))
    )
    (net (code "157") (name "TDO") (class "Default")
      (node (ref "JTAG") (pin "6") (pinfunction "6_6") (pintype "bidirectional"))
      (node (ref "U7") (pin "30") (pinfunction "PB30_30") (pintype "bidirectional"))
    )
    (net (code "158") (name "TMS") (class "Default")
      (node (ref "JTAG") (pin "2") (pinfunction "2_2") (pintype "bidirectional"))
      (node (ref "R11") (pin "1") (pinfunction "1_1") (pintype "passive"))
      (node (ref "U7") (pin "31") (pinfunction "PB31_31") (pintype "bidirectional"))
    )
    (net (code "159") (name "TX") (class "Default")
      (node (ref "U7") (pin "2") (pinfunction "PA9_2") (pintype "bidirectional"))
    )
    (net (code "160") (name "USBOTGID") (class "Default")
      (node (ref "U7") (pin "129") (pinfunction "PB11_129") (pintype "bidirectional"))
      (node (ref "USB2") (pin "4") (pinfunction "ID_4") (pintype "bidirectional"))
    )
    (net (code "161") (name "USB_SENSE") (class "Default")
      (node (ref "R7") (pin "1") (pinfunction "1_1") (pintype "passive"))
      (node (ref "U1") (pin "19") (pinfunction "AD2/GIO9_19") (pintype "bidirectional"))
      (node (ref "U7") (pin "19") (pinfunction "PD6_19") (pintype "bidirectional"))
    )
    (net (code "162") (name "WCLK") (class "Default")
      (node (ref "L9") (pin "1") (pinfunction "1_1") (pintype "passive"))
      (node (ref "U3") (pin "3") (pinfunction "WCLK_3") (pintype "bidirectional"))
    )
    (net (code "163") (name "unconnected-(CC_DEBUG-Pad3)") (class "Default")
      (node (ref "CC_DEBUG") (pin "3") (pinfunction "3_3") (pintype "bidirectional"))
    )
    (net (code "164") (name "unconnected-(CC_DEBUG-Pad4)") (class "Default")
      (node (ref "CC_DEBUG") (pin "4") (pinfunction "4_4") (pintype "bidirectional"))
    )
    (net (code "165") (name "unconnected-(ERASE-Pad2)") (class "Default")
      (node (ref "ERASE") (pin "2") (pinfunction "2_2") (pintype "bidirectional"))
    )
    (net (code "166") (name "unconnected-(ERASE-Pad4)") (class "Default")
      (node (ref "ERASE") (pin "4") (pinfunction "4_4") (pintype "bidirectional"))
    )
    (net (code "167") (name "unconnected-(JTAG-Pad7)") (class "Default")
      (node (ref "JTAG") (pin "7") (pinfunction "7_7") (pintype "bidirectional"))
    )
    (net (code "168") (name "unconnected-(LINE_IN-R_SW-Pad2)") (class "Default")
      (node (ref "LINE_IN") (pin "2") (pinfunction "R_SW_2") (pintype "bidirectional"))
    )
    (net (code "169") (name "unconnected-(PHONE_OUT-R_SW-Pad2)") (class "Default")
      (node (ref "PHONE_OUT") (pin "2") (pinfunction "R_SW_2") (pintype "bidirectional"))
    )
    (net (code "170") (name "unconnected-(RESET-Pad2)") (class "Default")
      (node (ref "RESET") (pin "2") (pinfunction "2_2") (pintype "bidirectional"))
    )
    (net (code "171") (name "unconnected-(RESET-Pad4)") (class "Default")
      (node (ref "RESET") (pin "4") (pinfunction "4_4") (pintype "bidirectional"))
    )
    (net (code "172") (name "unconnected-(U1-SCL{slash}GIO10-Pad32)") (class "Default")
      (node (ref "U1") (pin "32") (pinfunction "SCL/GIO10_32") (pintype "bidirectional"))
    )
    (net (code "173") (name "unconnected-(U1-SDA{slash}GIO11-Pad33)") (class "Default")
      (node (ref "U1") (pin "33") (pinfunction "SDA/GIO11_33") (pintype "bidirectional"))
    )
    (net (code "174") (name "unconnected-(U2-RXTX-Pad3)") (class "Default")
      (node (ref "U2") (pin "3") (pinfunction "RXTX_3") (pintype "bidirectional"))
    )
    (net (code "175") (name "unconnected-(U3-GPIO{slash}MFP5-Pad32)") (class "Default")
      (node (ref "U3") (pin "32") (pinfunction "GPIO/MFP5_32") (pintype "bidirectional"))
    )
    (net (code "176") (name "unconnected-(U3-IN2_L-Pad15)") (class "Default")
      (node (ref "U3") (pin "15") (pinfunction "IN2_L_15") (pintype "bidirectional"))
    )
    (net (code "177") (name "unconnected-(U3-IN2_R-Pad16)") (class "Default")
      (node (ref "U3") (pin "16") (pinfunction "IN2_R_16") (pintype "bidirectional"))
    )
    (net (code "178") (name "unconnected-(U3-IN3_L-Pad20)") (class "Default")
      (node (ref "U3") (pin "20") (pinfunction "IN3_L_20") (pintype "bidirectional"))
    )
    (net (code "179") (name "unconnected-(U3-IN3_R-Pad21)") (class "Default")
      (node (ref "U3") (pin "21") (pinfunction "IN3_R_21") (pintype "bidirectional"))
    )
    (net (code "180") (name "unconnected-(U3-MICBIAS-Pad19)") (class "Default")
      (node (ref "U3") (pin "19") (pinfunction "MICBIAS_19") (pintype "bidirectional"))
    )
    (net (code "181") (name "unconnected-(U7A-PA0-Pad23)") (class "Default")
      (node (ref "U7") (pin "23") (pinfunction "PA0_23") (pintype "bidirectional"))
    )
    (net (code "182") (name "unconnected-(U7A-PA1-Pad24)") (class "Default")
      (node (ref "U7") (pin "24") (pinfunction "PA1_24") (pintype "bidirectional"))
    )
    (net (code "183") (name "unconnected-(U7A-PA3-Pad84)") (class "Default")
      (node (ref "U7") (pin "84") (pinfunction "PA3_84") (pintype "bidirectional"))
    )
    (net (code "184") (name "unconnected-(U7A-PA4-Pad83)") (class "Default")
      (node (ref "U7") (pin "83") (pinfunction "PA4_83") (pintype "bidirectional"))
    )
    (net (code "185") (name "unconnected-(U7A-PA5-Pad25)") (class "Default")
      (node (ref "U7") (pin "25") (pinfunction "PA5_25") (pintype "bidirectional"))
    )
    (net (code "186") (name "unconnected-(U7A-PA6-Pad82)") (class "Default")
      (node (ref "U7") (pin "82") (pinfunction "PA6_82") (pintype "bidirectional"))
    )
    (net (code "187") (name "unconnected-(U7A-PA10-Pad3)") (class "Default")
      (node (ref "U7") (pin "3") (pinfunction "PA10_3") (pintype "bidirectional"))
    )
    (net (code "188") (name "unconnected-(U7A-PA11-Pad4)") (class "Default")
      (node (ref "U7") (pin "4") (pinfunction "PA11_4") (pintype "bidirectional"))
    )
    (net (code "189") (name "unconnected-(U7A-PA12-Pad5)") (class "Default")
      (node (ref "U7") (pin "5") (pinfunction "PA12_5") (pintype "bidirectional"))
    )
    (net (code "190") (name "unconnected-(U7A-PA13-Pad6)") (class "Default")
      (node (ref "U7") (pin "6") (pinfunction "PA13_6") (pintype "bidirectional"))
    )
    (net (code "191") (name "unconnected-(U7A-PA14-Pad7)") (class "Default")
      (node (ref "U7") (pin "7") (pinfunction "PA14_7") (pintype "bidirectional"))
    )
    (net (code "192") (name "unconnected-(U7A-PA15-Pad8)") (class "Default")
      (node (ref "U7") (pin "8") (pinfunction "PA15_8") (pintype "bidirectional"))
    )
    (net (code "193") (name "unconnected-(U7A-PA16-Pad78)") (class "Default")
      (node (ref "U7") (pin "78") (pinfunction "PA16_78") (pintype "bidirectional"))
    )
    (net (code "194") (name "unconnected-(U7A-PA17-Pad9)") (class "Default")
      (node (ref "U7") (pin "9") (pinfunction "PA17_9") (pintype "bidirectional"))
    )
    (net (code "195") (name "unconnected-(U7A-PA18-Pad70)") (class "Default")
      (node (ref "U7") (pin "70") (pinfunction "PA18_70") (pintype "bidirectional"))
    )
    (net (code "196") (name "unconnected-(U7A-PA19-Pad71)") (class "Default")
      (node (ref "U7") (pin "71") (pinfunction "PA19_71") (pintype "bidirectional"))
    )
    (net (code "197") (name "unconnected-(U7A-PA21-Pad107)") (class "Default")
      (node (ref "U7") (pin "107") (pinfunction "PA21_107") (pintype "bidirectional"))
    )
    (net (code "198") (name "unconnected-(U7A-PA22-Pad81)") (class "Default")
      (node (ref "U7") (pin "81") (pinfunction "PA22_81") (pintype "bidirectional"))
    )
    (net (code "199") (name "unconnected-(U7A-PA23-Pad80)") (class "Default")
      (node (ref "U7") (pin "80") (pinfunction "PA23_80") (pintype "bidirectional"))
    )
    (net (code "200") (name "unconnected-(U7A-PA24-Pad79)") (class "Default")
      (node (ref "U7") (pin "79") (pinfunction "PA24_79") (pintype "bidirectional"))
    )
    (net (code "201") (name "unconnected-(U7A-PA28-Pad111)") (class "Default")
      (node (ref "U7") (pin "111") (pinfunction "PA28_111") (pintype "bidirectional"))
    )
    (net (code "202") (name "unconnected-(U7A-PA29-Pad112)") (class "Default")
      (node (ref "U7") (pin "112") (pinfunction "PA29_112") (pintype "bidirectional"))
    )
    (net (code "203") (name "unconnected-(U7B-PB0-Pad113)") (class "Default")
      (node (ref "U7") (pin "113") (pinfunction "PB0_113") (pintype "bidirectional"))
    )
    (net (code "204") (name "unconnected-(U7B-PB1-Pad114)") (class "Default")
      (node (ref "U7") (pin "114") (pinfunction "PB1_114") (pintype "bidirectional"))
    )
    (net (code "205") (name "unconnected-(U7B-PB2-Pad115)") (class "Default")
      (node (ref "U7") (pin "115") (pinfunction "PB2_115") (pintype "bidirectional"))
    )
    (net (code "206") (name "unconnected-(U7B-PB3-Pad118)") (class "Default")
      (node (ref "U7") (pin "118") (pinfunction "PB3_118") (pintype "bidirectional"))
    )
    (net (code "207") (name "unconnected-(U7B-PB4-Pad119)") (class "Default")
      (node (ref "U7") (pin "119") (pinfunction "PB4_119") (pintype "bidirectional"))
    )
    (net (code "208") (name "unconnected-(U7B-PB5-Pad120)") (class "Default")
      (node (ref "U7") (pin "120") (pinfunction "PB5_120") (pintype "bidirectional"))
    )
    (net (code "209") (name "unconnected-(U7B-PB6-Pad121)") (class "Default")
      (node (ref "U7") (pin "121") (pinfunction "PB6_121") (pintype "bidirectional"))
    )
    (net (code "210") (name "unconnected-(U7B-PB7-Pad122)") (class "Default")
      (node (ref "U7") (pin "122") (pinfunction "PB7_122") (pintype "bidirectional"))
    )
    (net (code "211") (name "unconnected-(U7B-PB8-Pad123)") (class "Default")
      (node (ref "U7") (pin "123") (pinfunction "PB8_123") (pintype "bidirectional"))
    )
    (net (code "212") (name "unconnected-(U7B-PB9-Pad127)") (class "Default")
      (node (ref "U7") (pin "127") (pinfunction "PB9_127") (pintype "bidirectional"))
    )
    (net (code "213") (name "unconnected-(U7B-PB10-Pad128)") (class "Default")
      (node (ref "U7") (pin "128") (pinfunction "PB10_128") (pintype "bidirectional"))
    )
    (net (code "214") (name "unconnected-(U7B-PB12-Pad86)") (class "Default")
      (node (ref "U7") (pin "86") (pinfunction "PB12_86") (pintype "bidirectional"))
    )
    (net (code "215") (name "unconnected-(U7B-PB13-Pad87)") (class "Default")
      (node (ref "U7") (pin "87") (pinfunction "PB13_87") (pintype "bidirectional"))
    )
    (net (code "216") (name "unconnected-(U7B-PB15-Pad76)") (class "Default")
      (node (ref "U7") (pin "76") (pinfunction "PB15_76") (pintype "bidirectional"))
    )
    (net (code "217") (name "unconnected-(U7B-PB16-Pad77)") (class "Default")
      (node (ref "U7") (pin "77") (pinfunction "PB16_77") (pintype "bidirectional"))
    )
    (net (code "218") (name "unconnected-(U7B-PB17-Pad88)") (class "Default")
      (node (ref "U7") (pin "88") (pinfunction "PB17_88") (pintype "bidirectional"))
    )
    (net (code "219") (name "unconnected-(U7B-PB18-Pad89)") (class "Default")
      (node (ref "U7") (pin "89") (pinfunction "PB18_89") (pintype "bidirectional"))
    )
    (net (code "220") (name "unconnected-(U7B-PB19-Pad90)") (class "Default")
      (node (ref "U7") (pin "90") (pinfunction "PB19_90") (pintype "bidirectional"))
    )
    (net (code "221") (name "unconnected-(U7B-PB20-Pad91)") (class "Default")
      (node (ref "U7") (pin "91") (pinfunction "PB20_91") (pintype "bidirectional"))
    )
    (net (code "222") (name "unconnected-(U7B-PB21-Pad92)") (class "Default")
      (node (ref "U7") (pin "92") (pinfunction "PB21_92") (pintype "bidirectional"))
    )
    (net (code "223") (name "unconnected-(U7B-PB22-Pad141)") (class "Default")
      (node (ref "U7") (pin "141") (pinfunction "PB22_141") (pintype "bidirectional"))
    )
    (net (code "224") (name "unconnected-(U7B-PB23-Pad142)") (class "Default")
      (node (ref "U7") (pin "142") (pinfunction "PB23_142") (pintype "bidirectional"))
    )
    (net (code "225") (name "unconnected-(U7B-PB24-Pad143)") (class "Default")
      (node (ref "U7") (pin "143") (pinfunction "PB24_143") (pintype "bidirectional"))
    )
    (net (code "226") (name "unconnected-(U7B-PB25-Pad144)") (class "Default")
      (node (ref "U7") (pin "144") (pinfunction "PB25_144") (pintype "bidirectional"))
    )
    (net (code "227") (name "unconnected-(U7B-PB26-Pad1)") (class "Default")
      (node (ref "U7") (pin "1") (pinfunction "PB26_1") (pintype "bidirectional"))
    )
    (net (code "228") (name "unconnected-(U7B-PB27-Pad68)") (class "Default")
      (node (ref "U7") (pin "68") (pinfunction "PB27_68") (pintype "bidirectional"))
    )
    (net (code "229") (name "unconnected-(U7C-PC1-Pad55)") (class "Default")
      (node (ref "U7") (pin "55") (pinfunction "PC1_55") (pintype "bidirectional"))
    )
    (net (code "230") (name "unconnected-(U7C-PC2-Pad59)") (class "Default")
      (node (ref "U7") (pin "59") (pinfunction "PC2_59") (pintype "bidirectional"))
    )
    (net (code "231") (name "unconnected-(U7C-PC3-Pad60)") (class "Default")
      (node (ref "U7") (pin "60") (pinfunction "PC3_60") (pintype "bidirectional"))
    )
    (net (code "232") (name "unconnected-(U7C-PC4-Pad116)") (class "Default")
      (node (ref "U7") (pin "116") (pinfunction "PC4_116") (pintype "bidirectional"))
    )
    (net (code "233") (name "unconnected-(U7C-PC5-Pad63)") (class "Default")
      (node (ref "U7") (pin "63") (pinfunction "PC5_63") (pintype "bidirectional"))
    )
    (net (code "234") (name "unconnected-(U7C-PC6-Pad64)") (class "Default")
      (node (ref "U7") (pin "64") (pinfunction "PC6_64") (pintype "bidirectional"))
    )
    (net (code "235") (name "unconnected-(U7C-PC7-Pad65)") (class "Default")
      (node (ref "U7") (pin "65") (pinfunction "PC7_65") (pintype "bidirectional"))
    )
    (net (code "236") (name "unconnected-(U7C-PC10-Pad117)") (class "Default")
      (node (ref "U7") (pin "117") (pinfunction "PC10_117") (pintype "bidirectional"))
    )
    (net (code "237") (name "unconnected-(U7C-PC11-Pad93)") (class "Default")
      (node (ref "U7") (pin "93") (pinfunction "PC11_93") (pintype "bidirectional"))
    )
    (net (code "238") (name "unconnected-(U7C-PC12-Pad94)") (class "Default")
      (node (ref "U7") (pin "94") (pinfunction "PC12_94") (pintype "bidirectional"))
    )
    (net (code "239") (name "unconnected-(U7C-PC13-Pad95)") (class "Default")
      (node (ref "U7") (pin "95") (pinfunction "PC13_95") (pintype "bidirectional"))
    )
    (net (code "240") (name "unconnected-(U7C-PC14-Pad96)") (class "Default")
      (node (ref "U7") (pin "96") (pinfunction "PC14_96") (pintype "bidirectional"))
    )
    (net (code "241") (name "unconnected-(U7C-PC15-Pad97)") (class "Default")
      (node (ref "U7") (pin "97") (pinfunction "PC15_97") (pintype "bidirectional"))
    )
    (net (code "242") (name "unconnected-(U7C-PC16-Pad98)") (class "Default")
      (node (ref "U7") (pin "98") (pinfunction "PC16_98") (pintype "bidirectional"))
    )
    (net (code "243") (name "unconnected-(U7C-PC17-Pad99)") (class "Default")
      (node (ref "U7") (pin "99") (pinfunction "PC17_99") (pintype "bidirectional"))
    )
    (net (code "244") (name "unconnected-(U7C-PC18-Pad100)") (class "Default")
      (node (ref "U7") (pin "100") (pinfunction "PC18_100") (pintype "bidirectional"))
    )
    (net (code "245") (name "unconnected-(U7C-PC20-Pad131)") (class "Default")
      (node (ref "U7") (pin "131") (pinfunction "PC20_131") (pintype "bidirectional"))
    )
    (net (code "246") (name "unconnected-(U7C-PC26-Pad137)") (class "Default")
      (node (ref "U7") (pin "137") (pinfunction "PC26_137") (pintype "bidirectional"))
    )
    (net (code "247") (name "unconnected-(U7C-PC27-Pad138)") (class "Default")
      (node (ref "U7") (pin "138") (pinfunction "PC27_138") (pintype "bidirectional"))
    )
    (net (code "248") (name "unconnected-(U7C-PC29-Pad102)") (class "Default")
      (node (ref "U7") (pin "102") (pinfunction "PC29_102") (pintype "bidirectional"))
    )
    (net (code "249") (name "unconnected-(U7C-PC30-Pad103)") (class "Default")
      (node (ref "U7") (pin "103") (pinfunction "PC30_103") (pintype "bidirectional"))
    )
    (net (code "250") (name "unconnected-(U7D-PD0-Pad13)") (class "Default")
      (node (ref "U7") (pin "13") (pinfunction "PD0_13") (pintype "bidirectional"))
    )
    (net (code "251") (name "unconnected-(U7D-PD1-Pad14)") (class "Default")
      (node (ref "U7") (pin "14") (pinfunction "PD1_14") (pintype "bidirectional"))
    )
    (net (code "252") (name "unconnected-(U7D-PD4-Pad17)") (class "Default")
      (node (ref "U7") (pin "17") (pinfunction "PD4_17") (pintype "bidirectional"))
    )
    (net (code "253") (name "unconnected-(U7D-PD5-Pad18)") (class "Default")
      (node (ref "U7") (pin "18") (pinfunction "PD5_18") (pintype "bidirectional"))
    )
    (net (code "254") (name "unconnected-(U7F-NRST-Pad69)") (class "Default")
      (node (ref "U7") (pin "69") (pinfunction "NRST_69") (pintype "bidirectional"))
    )
    (net (code "255") (name "unconnected-(U7F-SHDN-Pad50)") (class "Default")
      (node (ref "U7") (pin "50") (pinfunction "SHDN_50") (pintype "bidirectional"))
    )
    (net (code "256") (name "unconnected-(U7F-TST-Pad51)") (class "Default")
      (node (ref "U7") (pin "51") (pinfunction "TST_51") (pintype "bidirectional"))
    )
    (net (code "257") (name "unconnected-(U7F-XIN32-Pad48)") (class "Default")
      (node (ref "U7") (pin "48") (pinfunction "XIN32_48") (pintype "bidirectional"))
    )
    (net (code "258") (name "unconnected-(U7F-XOUT32-Pad49)") (class "Default")
      (node (ref "U7") (pin "49") (pinfunction "XOUT32_49") (pintype "bidirectional"))
    )
    (net (code "259") (name "unconnected-(U8-SNS0-Pad32)") (class "Default")
      (node (ref "U8") (pin "32") (pinfunction "SNS0_32") (pintype "bidirectional"))
    )
    (net (code "260") (name "unconnected-(U8-SNS0K-Pad1)") (class "Default")
      (node (ref "U8") (pin "1") (pinfunction "SNS0K_1") (pintype "bidirectional"))
    )
    (net (code "261") (name "unconnected-(U8-SNS1-Pad2)") (class "Default")
      (node (ref "U8") (pin "2") (pinfunction "SNS1_2") (pintype "bidirectional"))
    )
    (net (code "262") (name "unconnected-(U8-SNS1K-Pad3)") (class "Default")
      (node (ref "U8") (pin "3") (pinfunction "SNS1K_3") (pintype "bidirectional"))
    )
    (net (code "263") (name "unconnected-(U8-SNS2-Pad7)") (class "Default")
      (node (ref "U8") (pin "7") (pinfunction "SNS2_7") (pintype "bidirectional"))
    )
    (net (code "264") (name "unconnected-(U8-SNS2K-Pad6)") (class "Default")
      (node (ref "U8") (pin "6") (pinfunction "SNS2K_6") (pintype "bidirectional"))
    )
    (net (code "265") (name "unconnected-(USB1-ID-Pad4)") (class "Default")
      (node (ref "USB1") (pin "4") (pinfunction "ID_4") (pintype "bidirectional"))
    )
  )
)
